# icyradio-upconverter.net
KiCad netlist of a schematic drawn in EAGLE
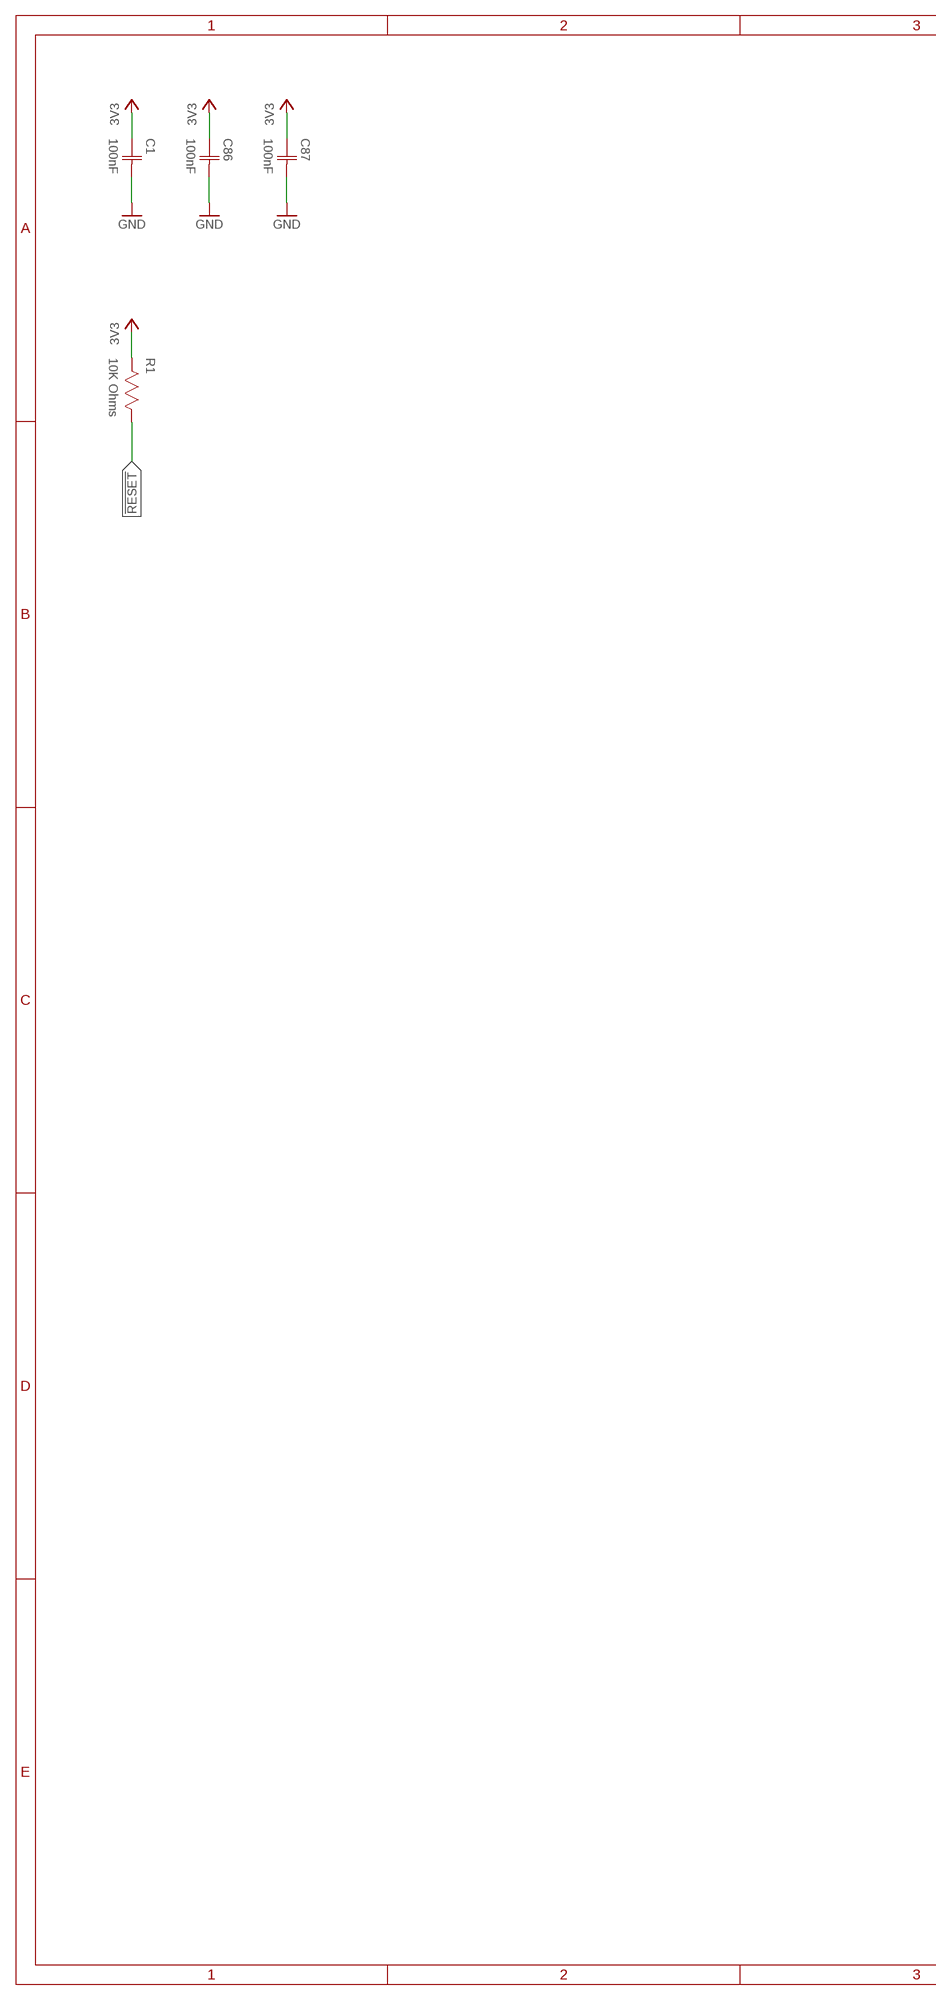
[diagram p0: schematic, sheet 1, part 1 of 2]
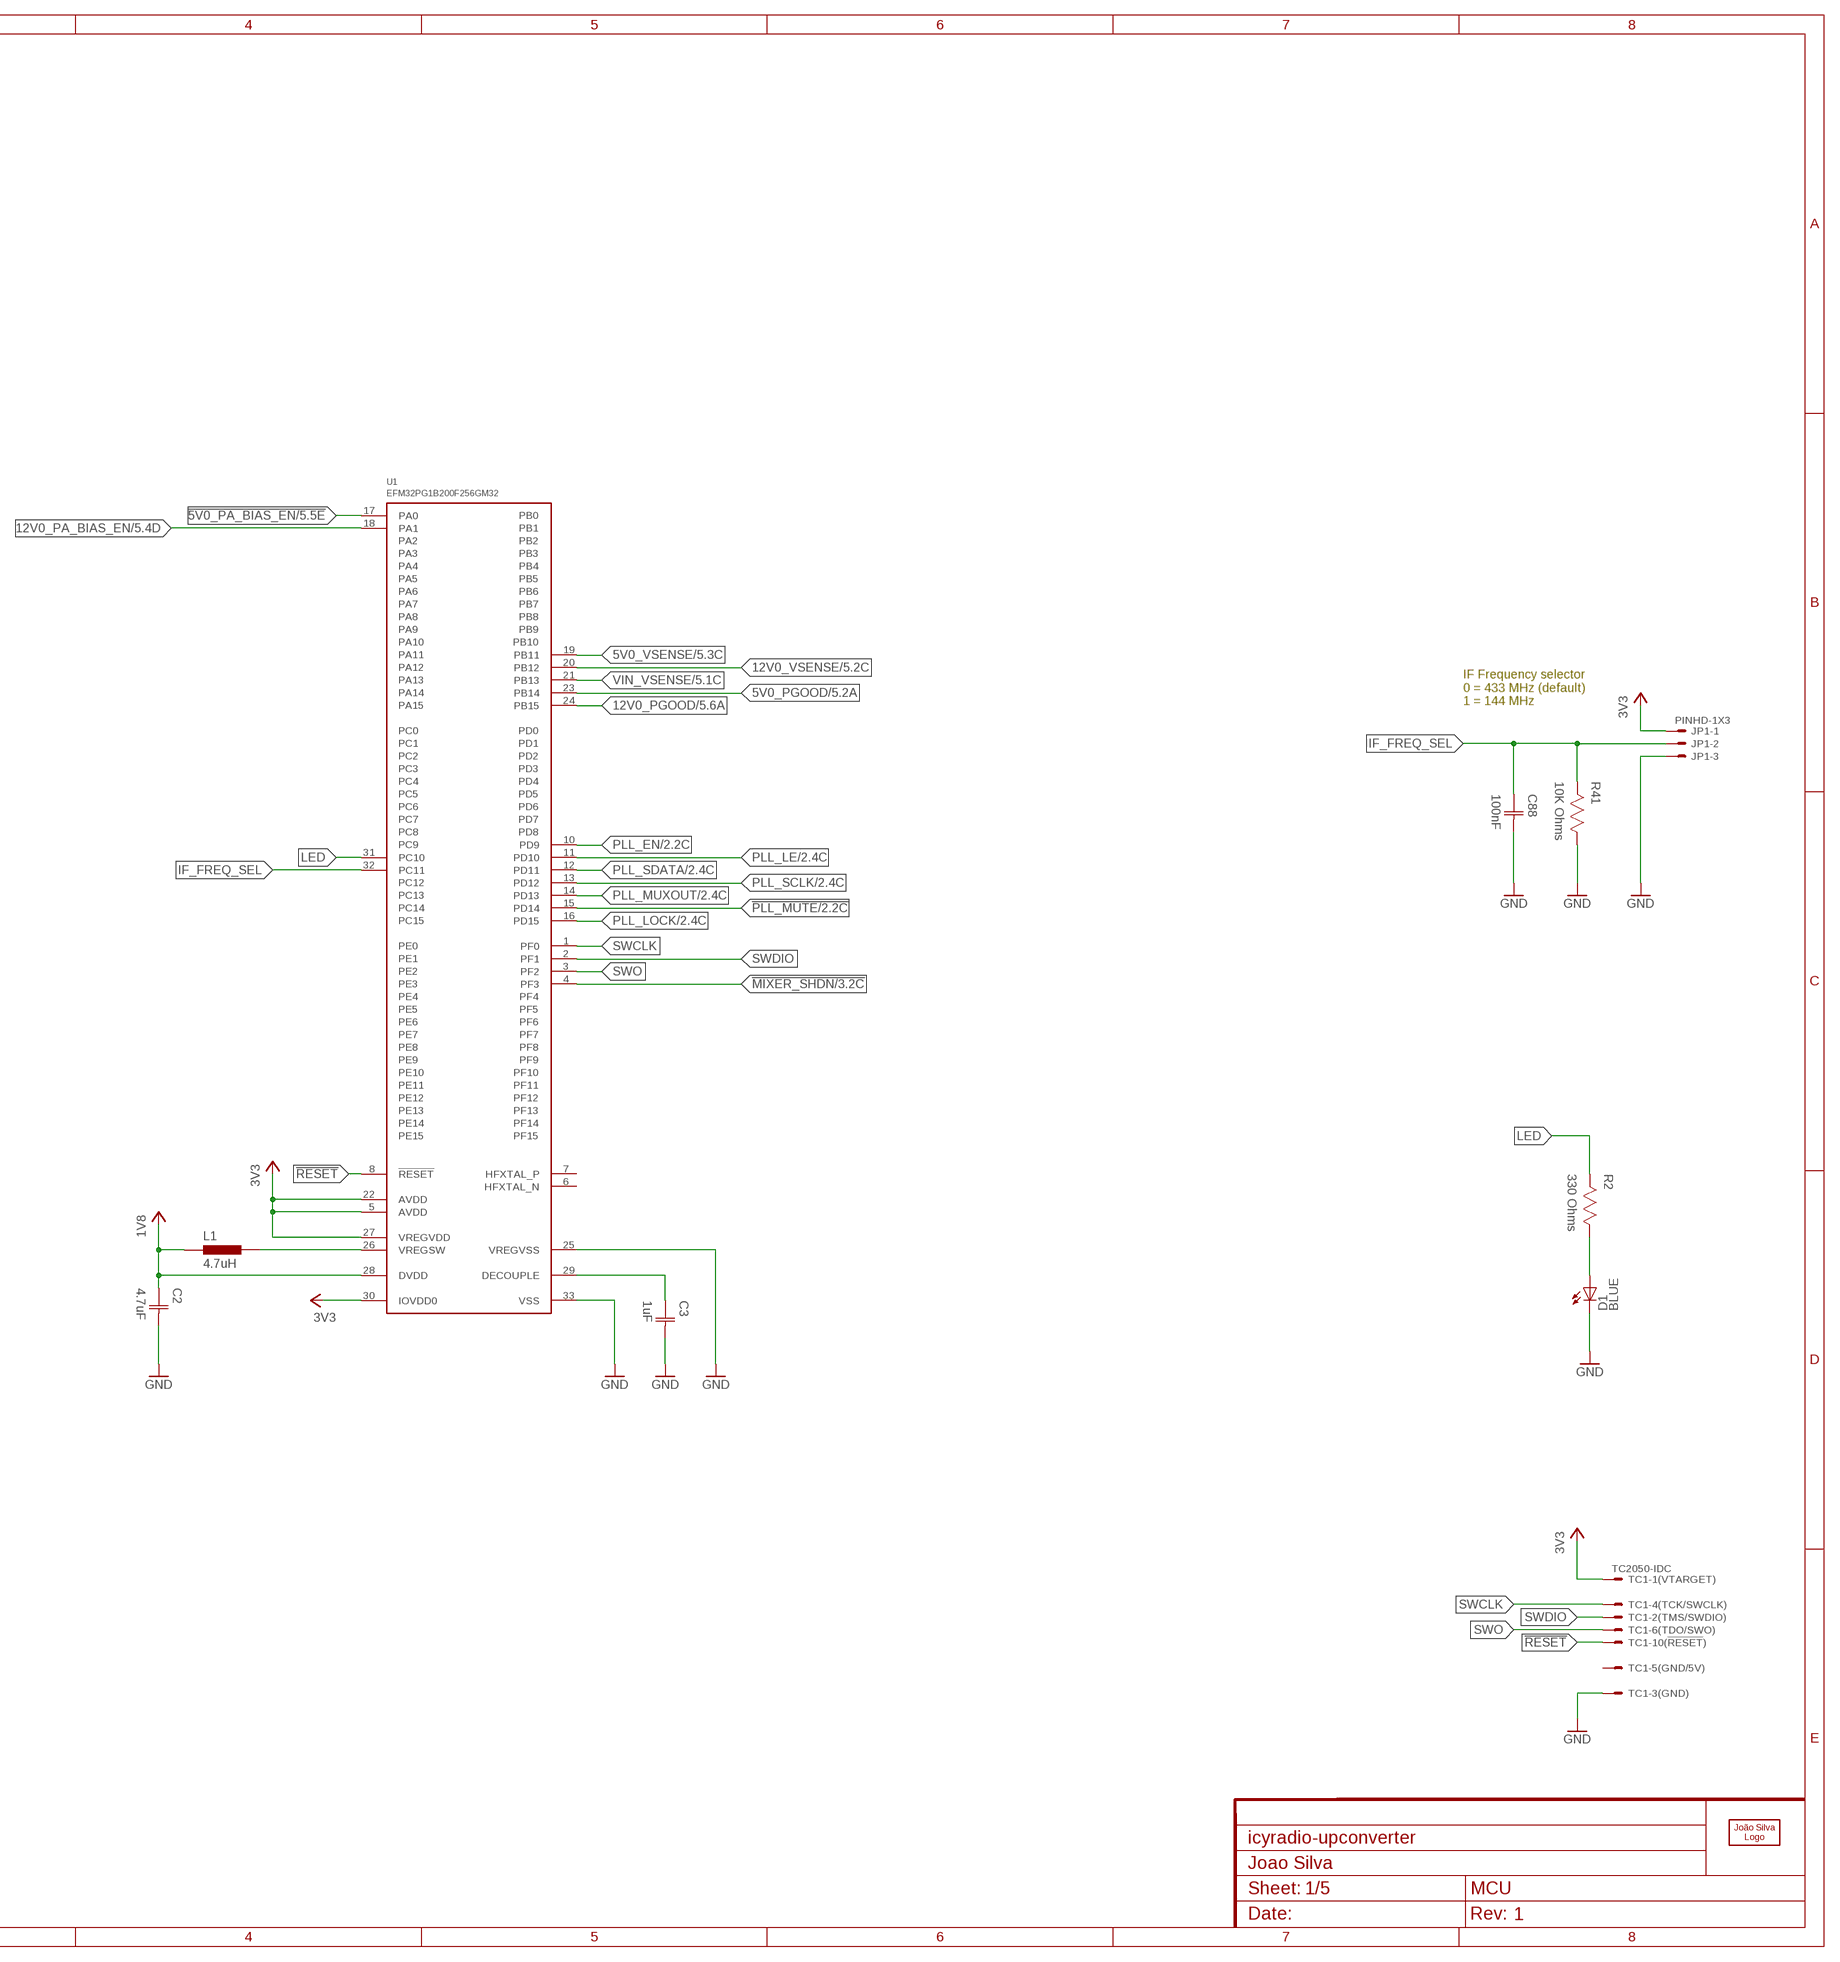
[diagram p1: schematic, sheet 1, part 2 of 2]
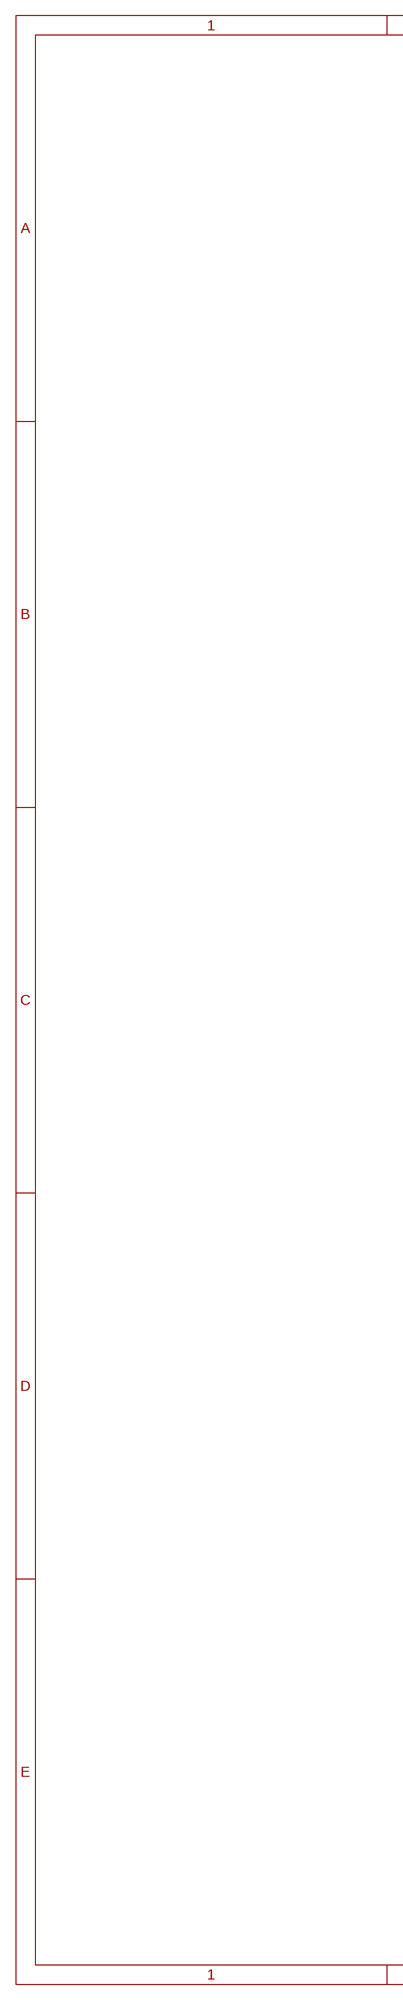
[diagram p2: schematic, sheet 2, part 1 of 2]
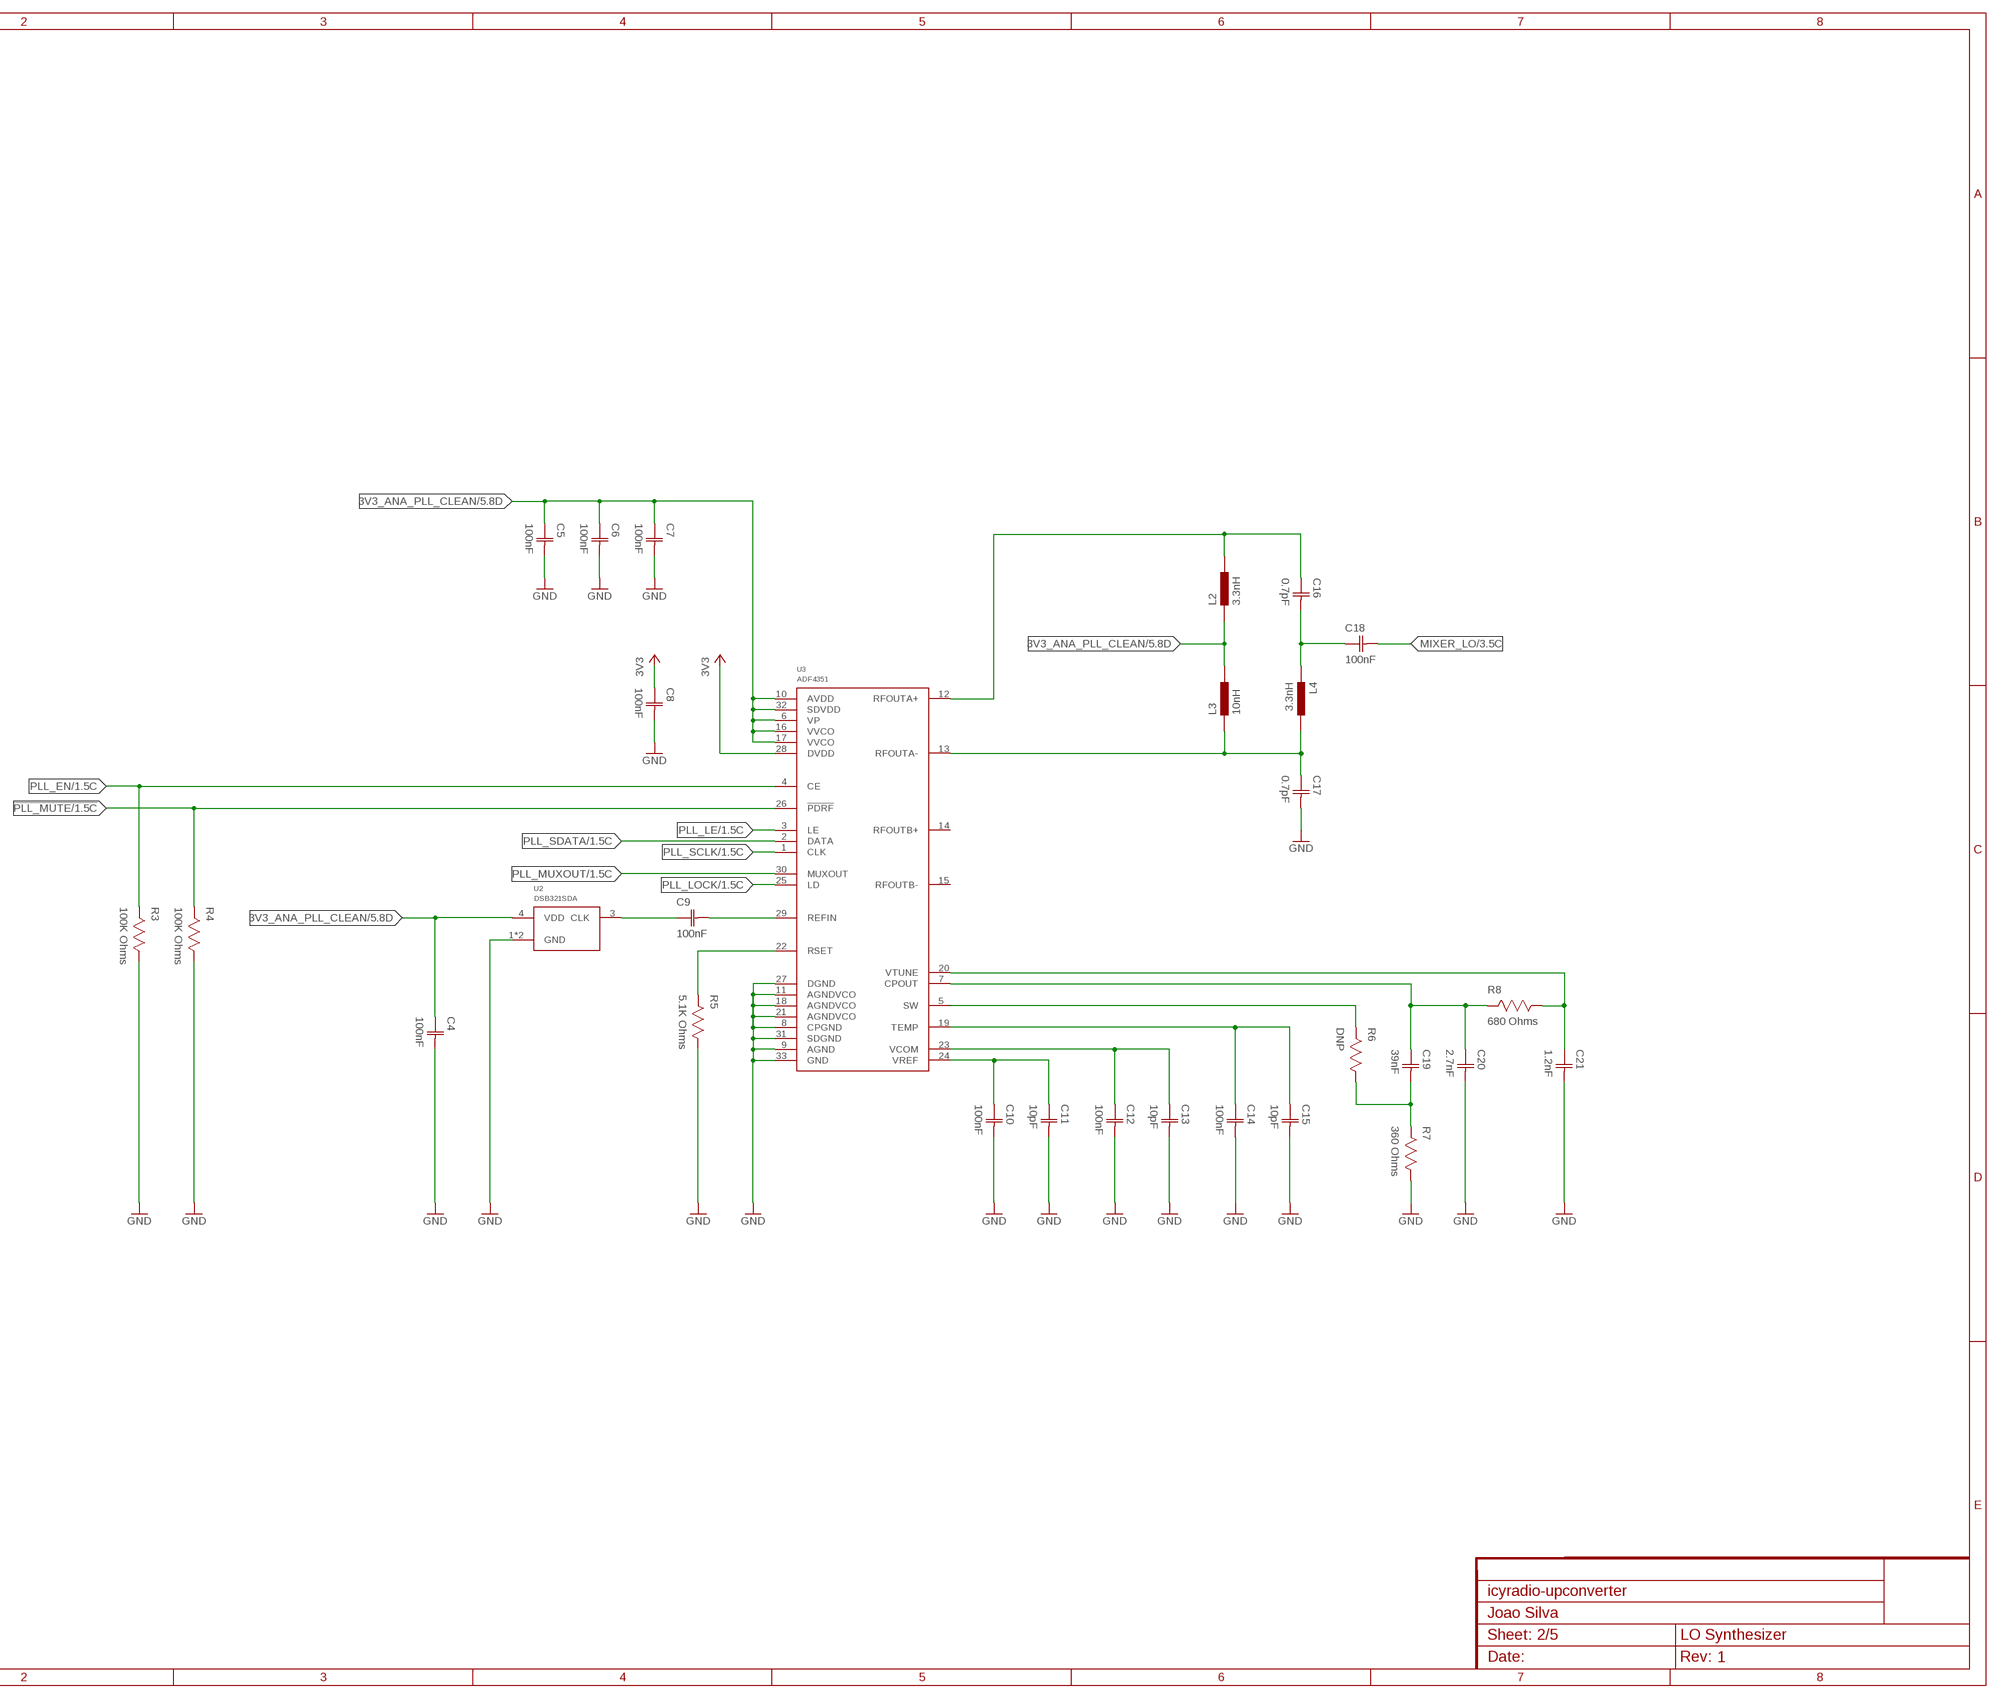
[diagram p3: schematic, sheet 2, part 2 of 2]
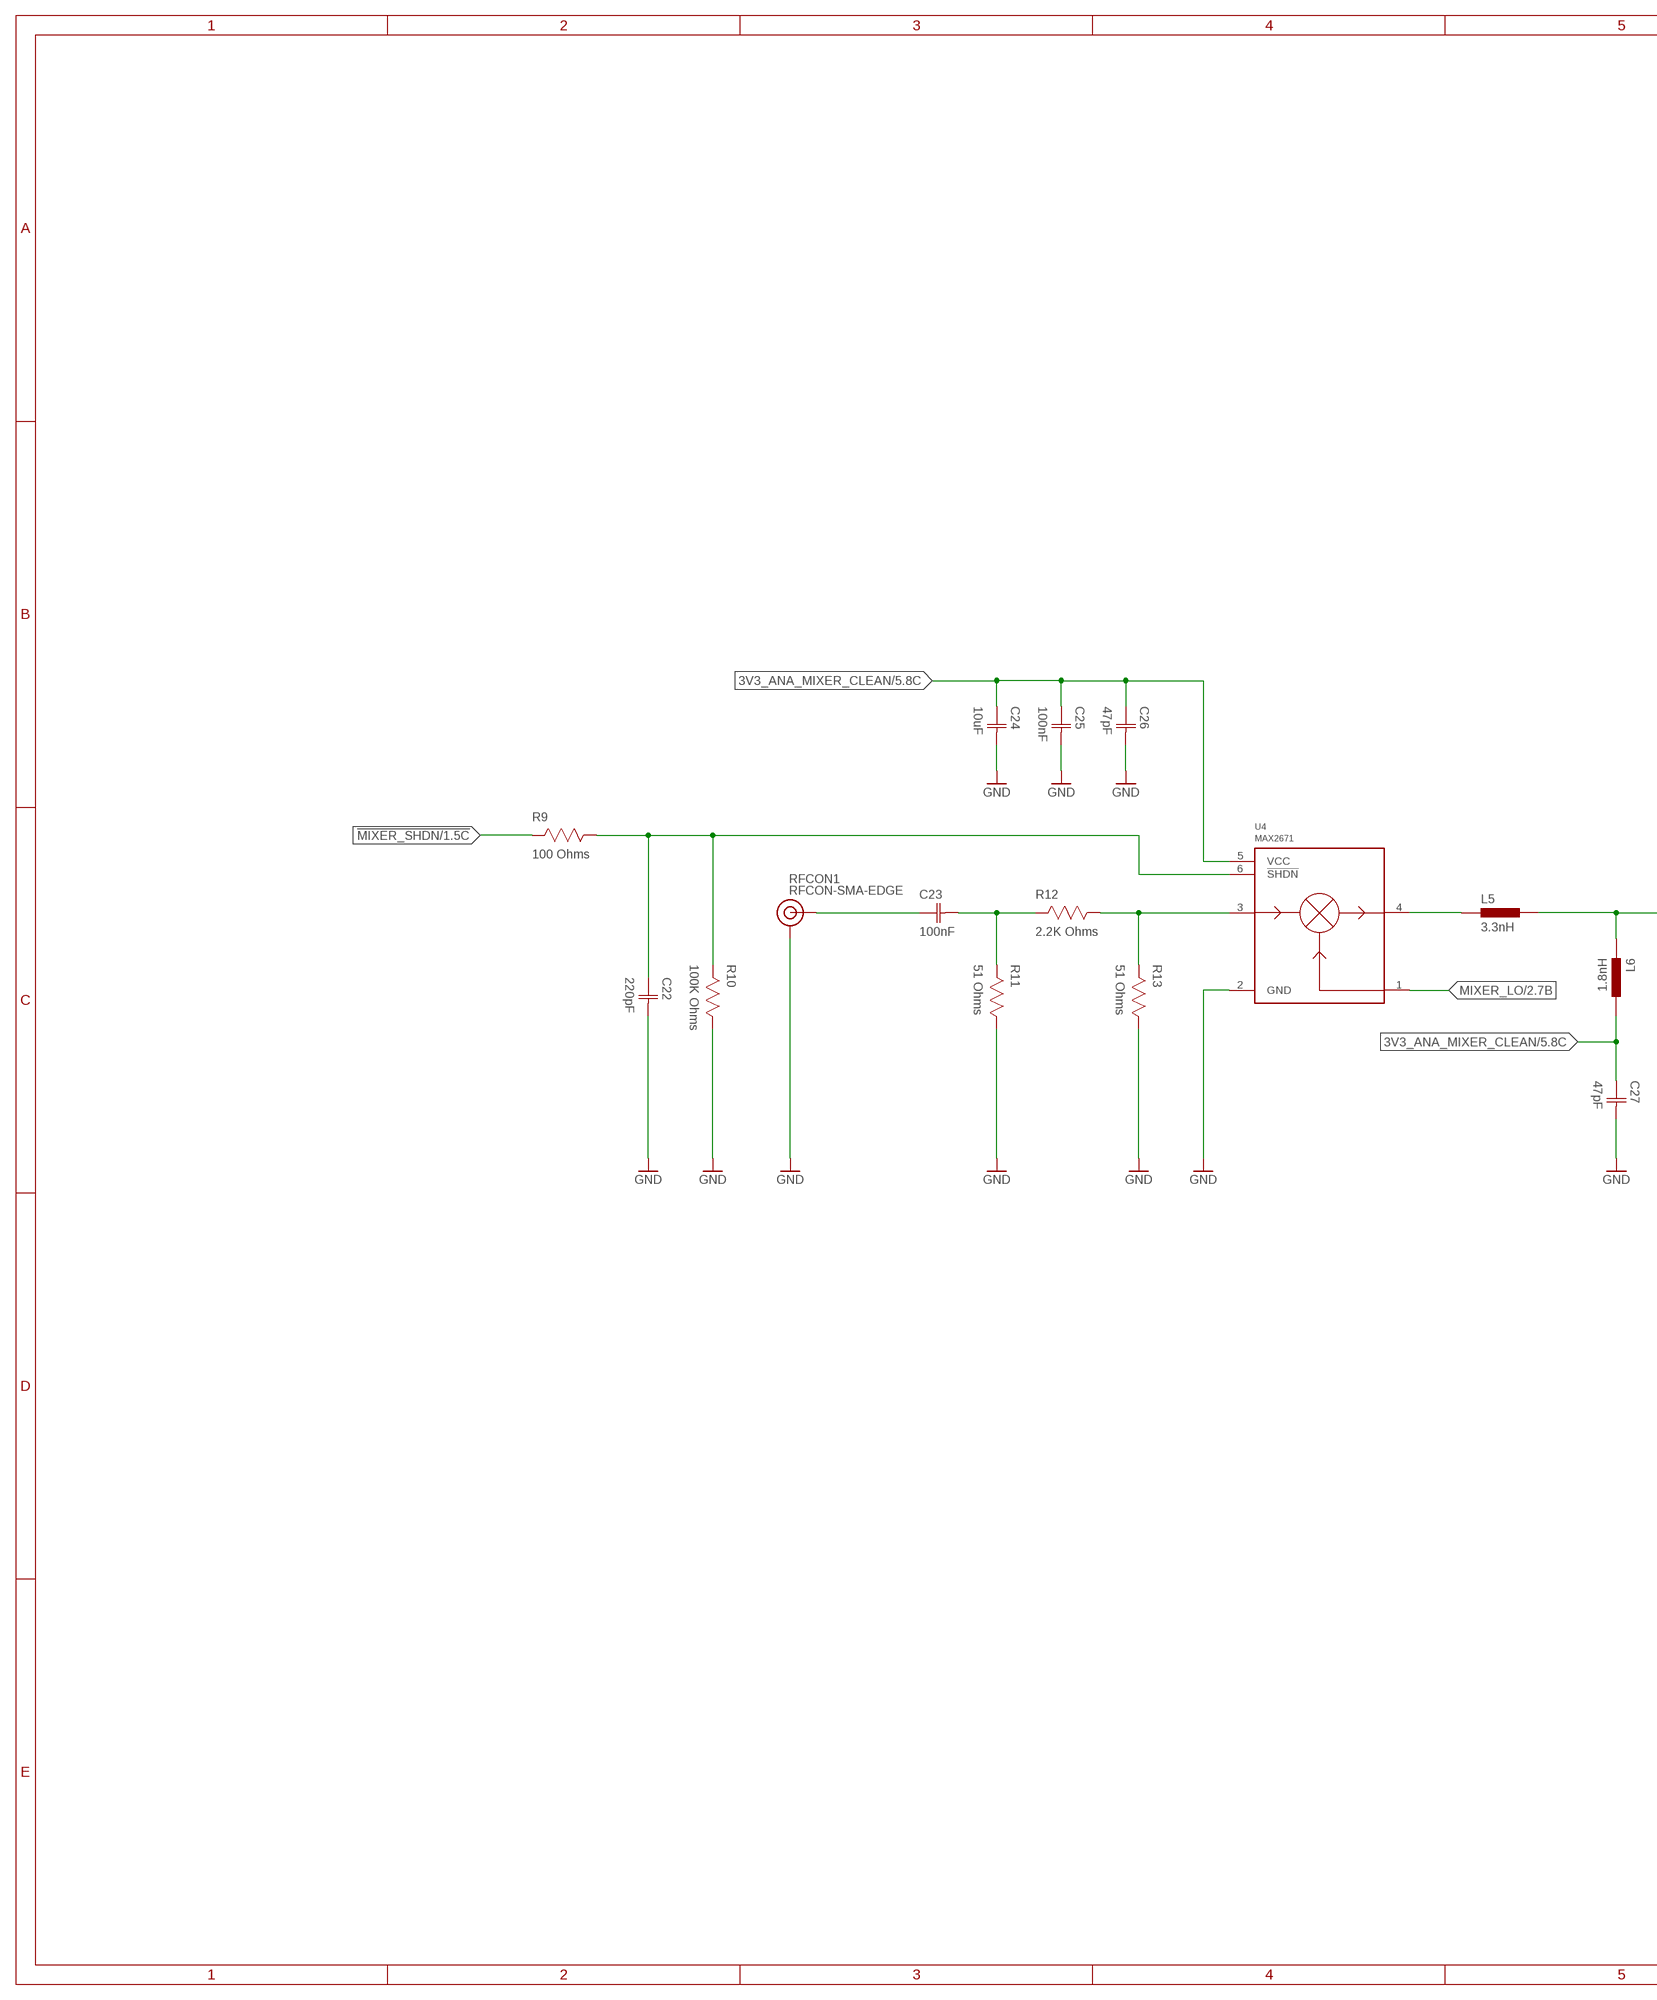
[diagram p4: schematic, sheet 3, part 1 of 2]
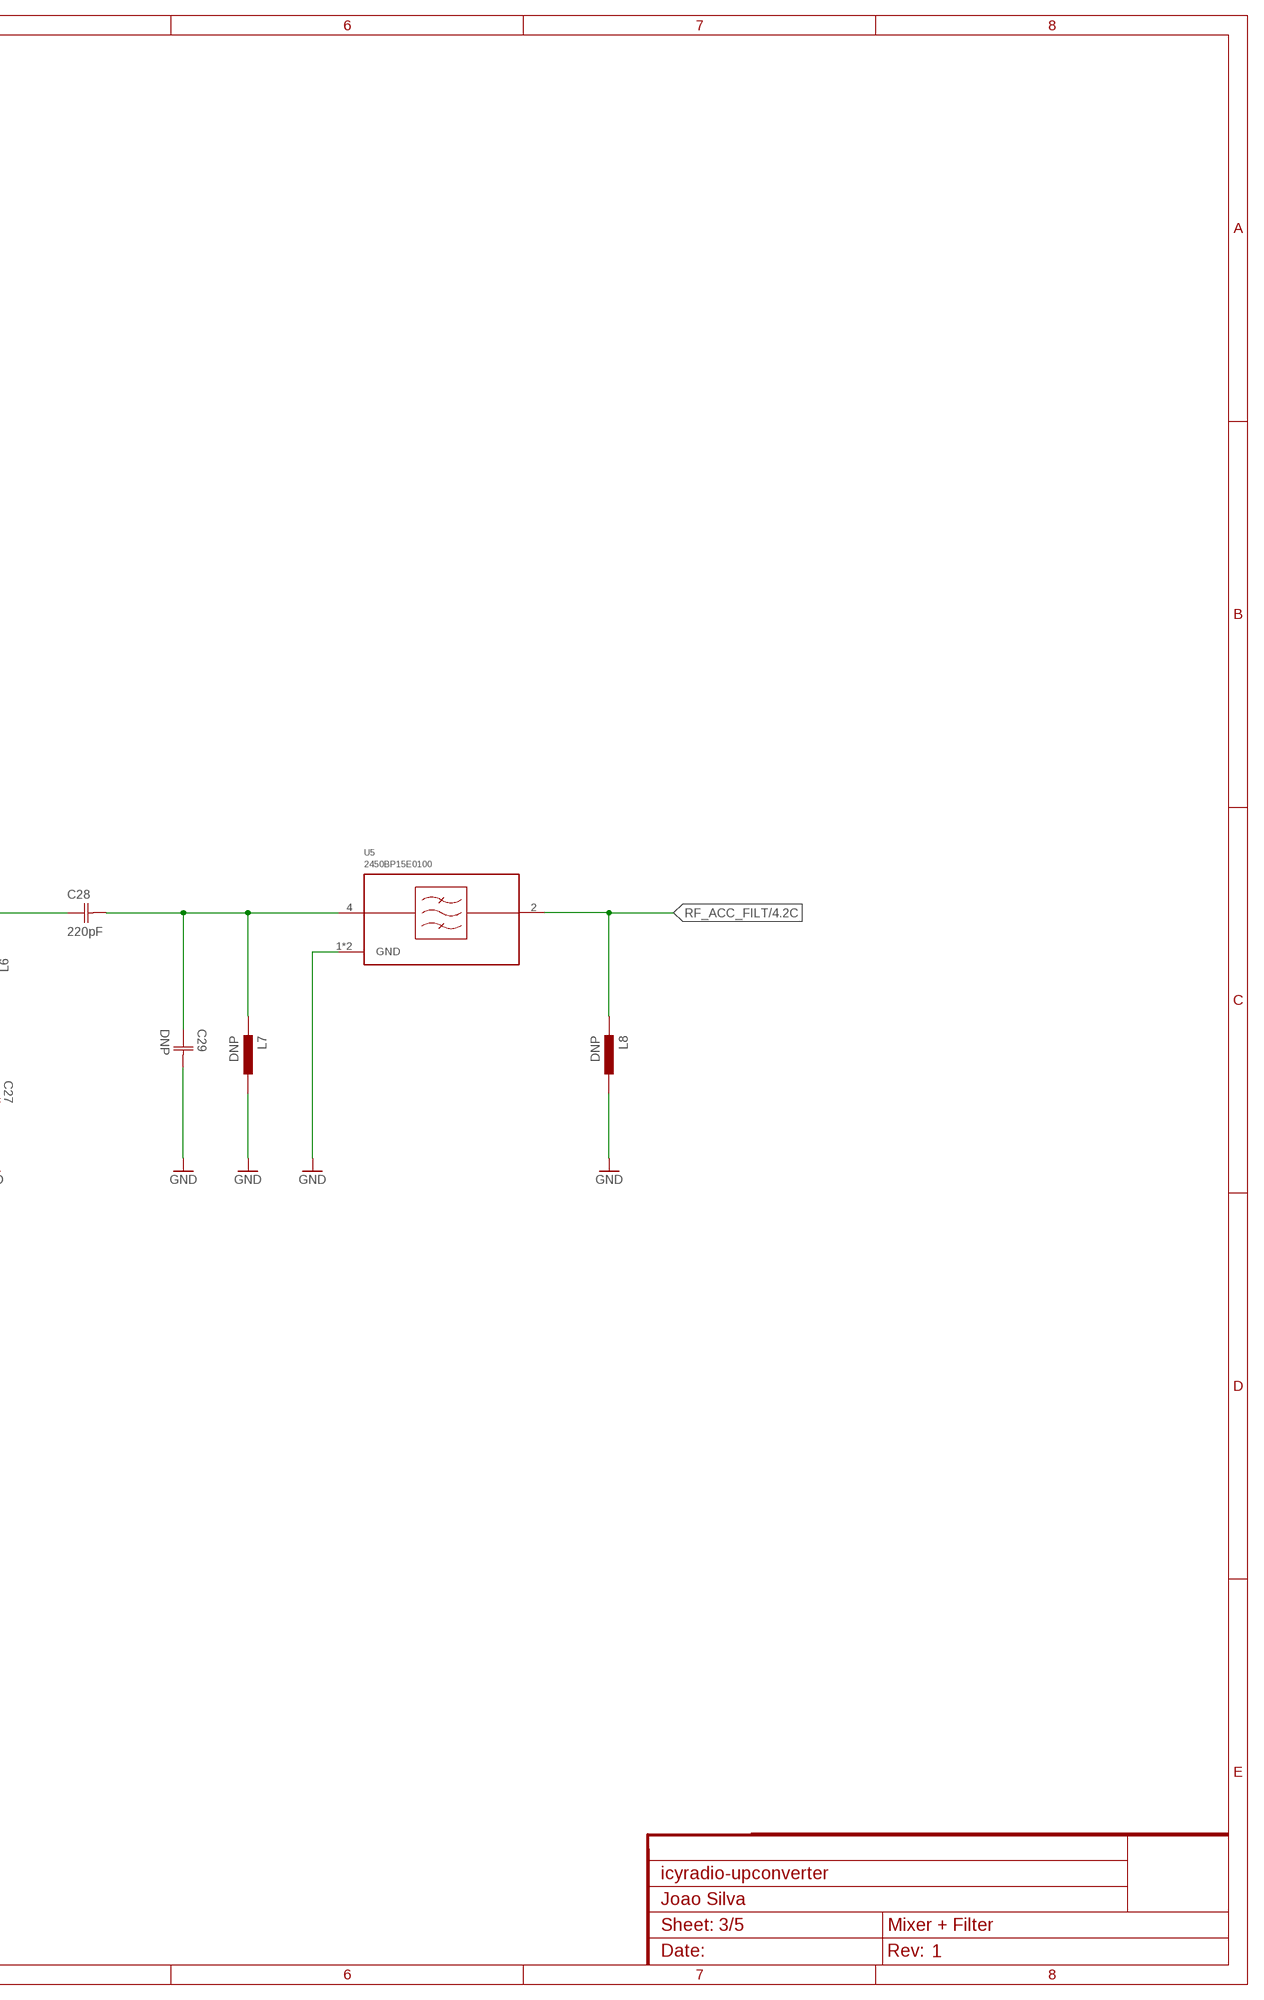
[diagram p5: schematic, sheet 3, part 2 of 2]
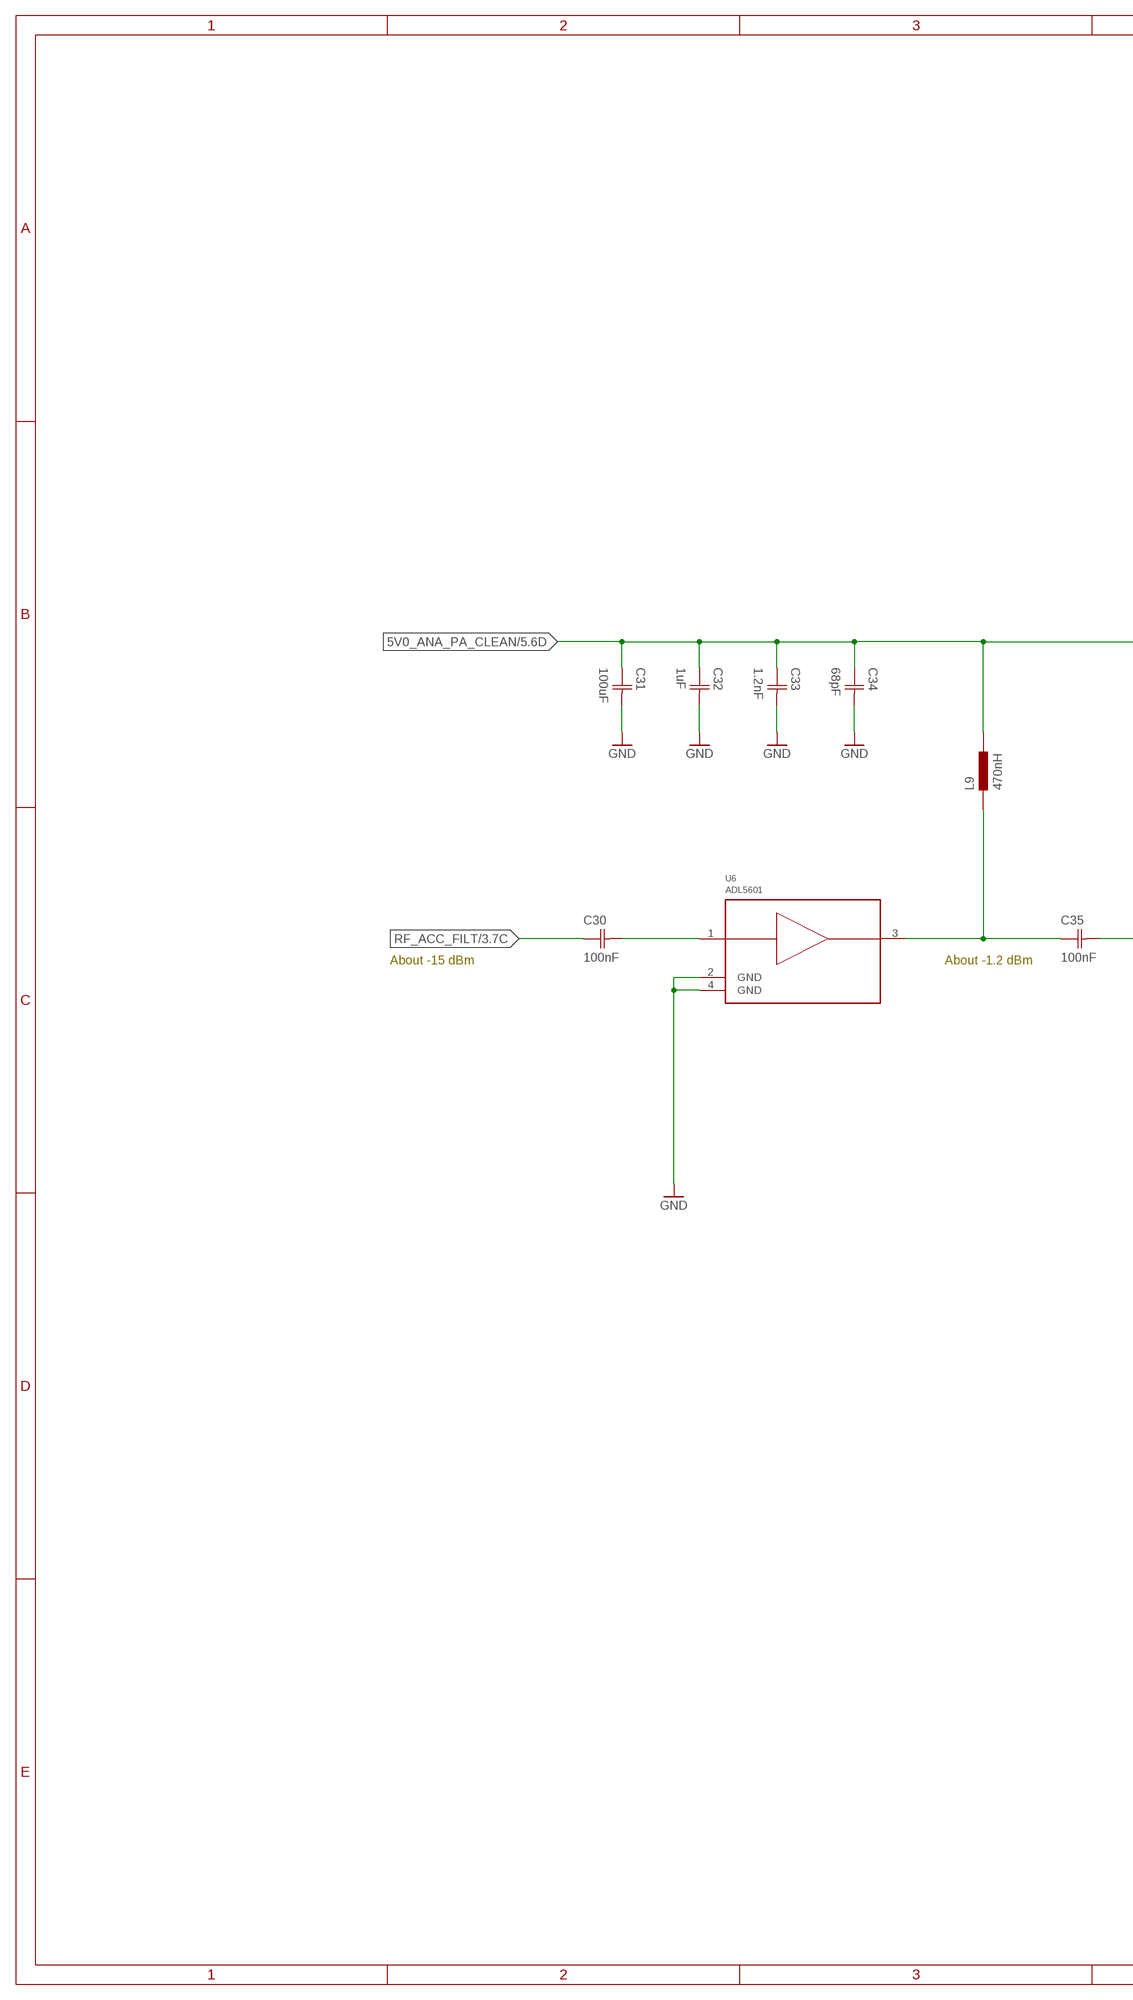
[diagram p6: schematic, sheet 4, part 1 of 2]
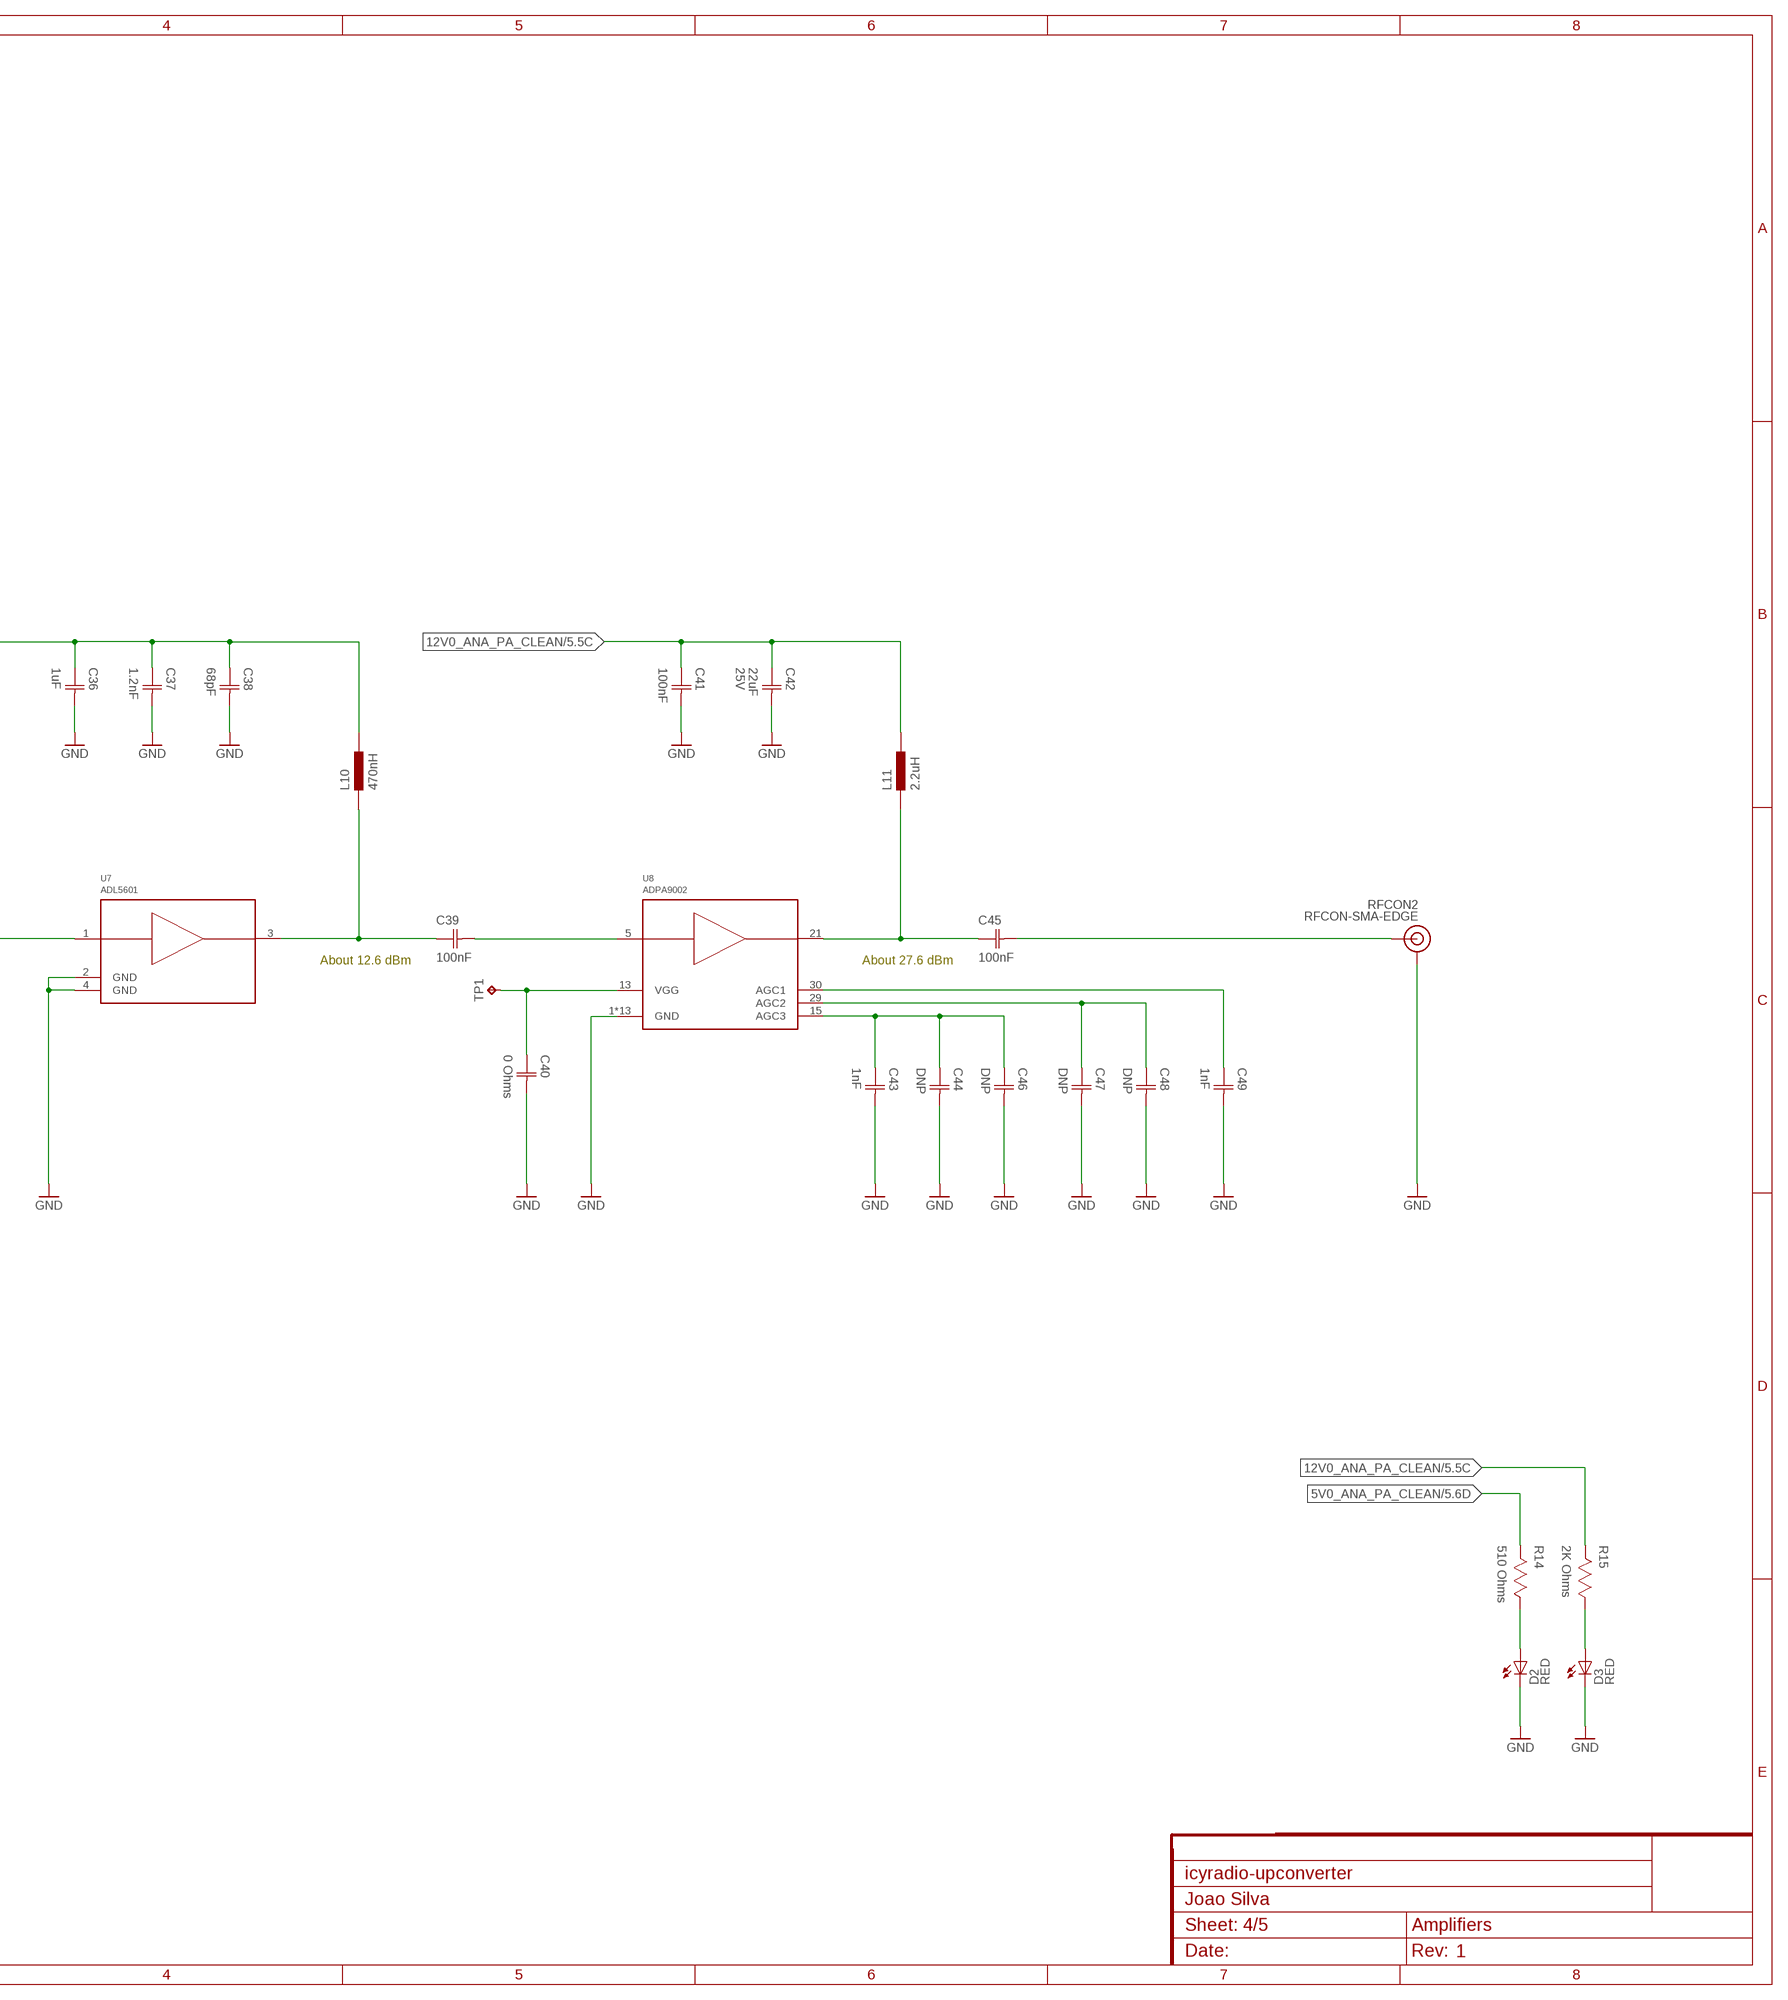
[diagram p7: schematic, sheet 4, part 2 of 2]
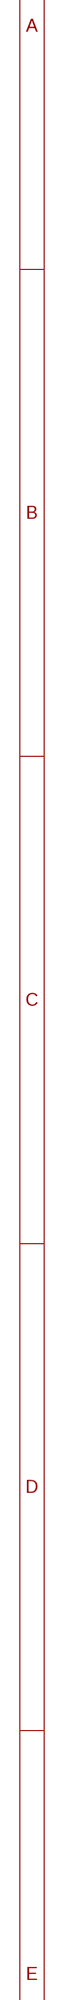
[diagram p8: schematic, sheet 5, part 1 of 2]
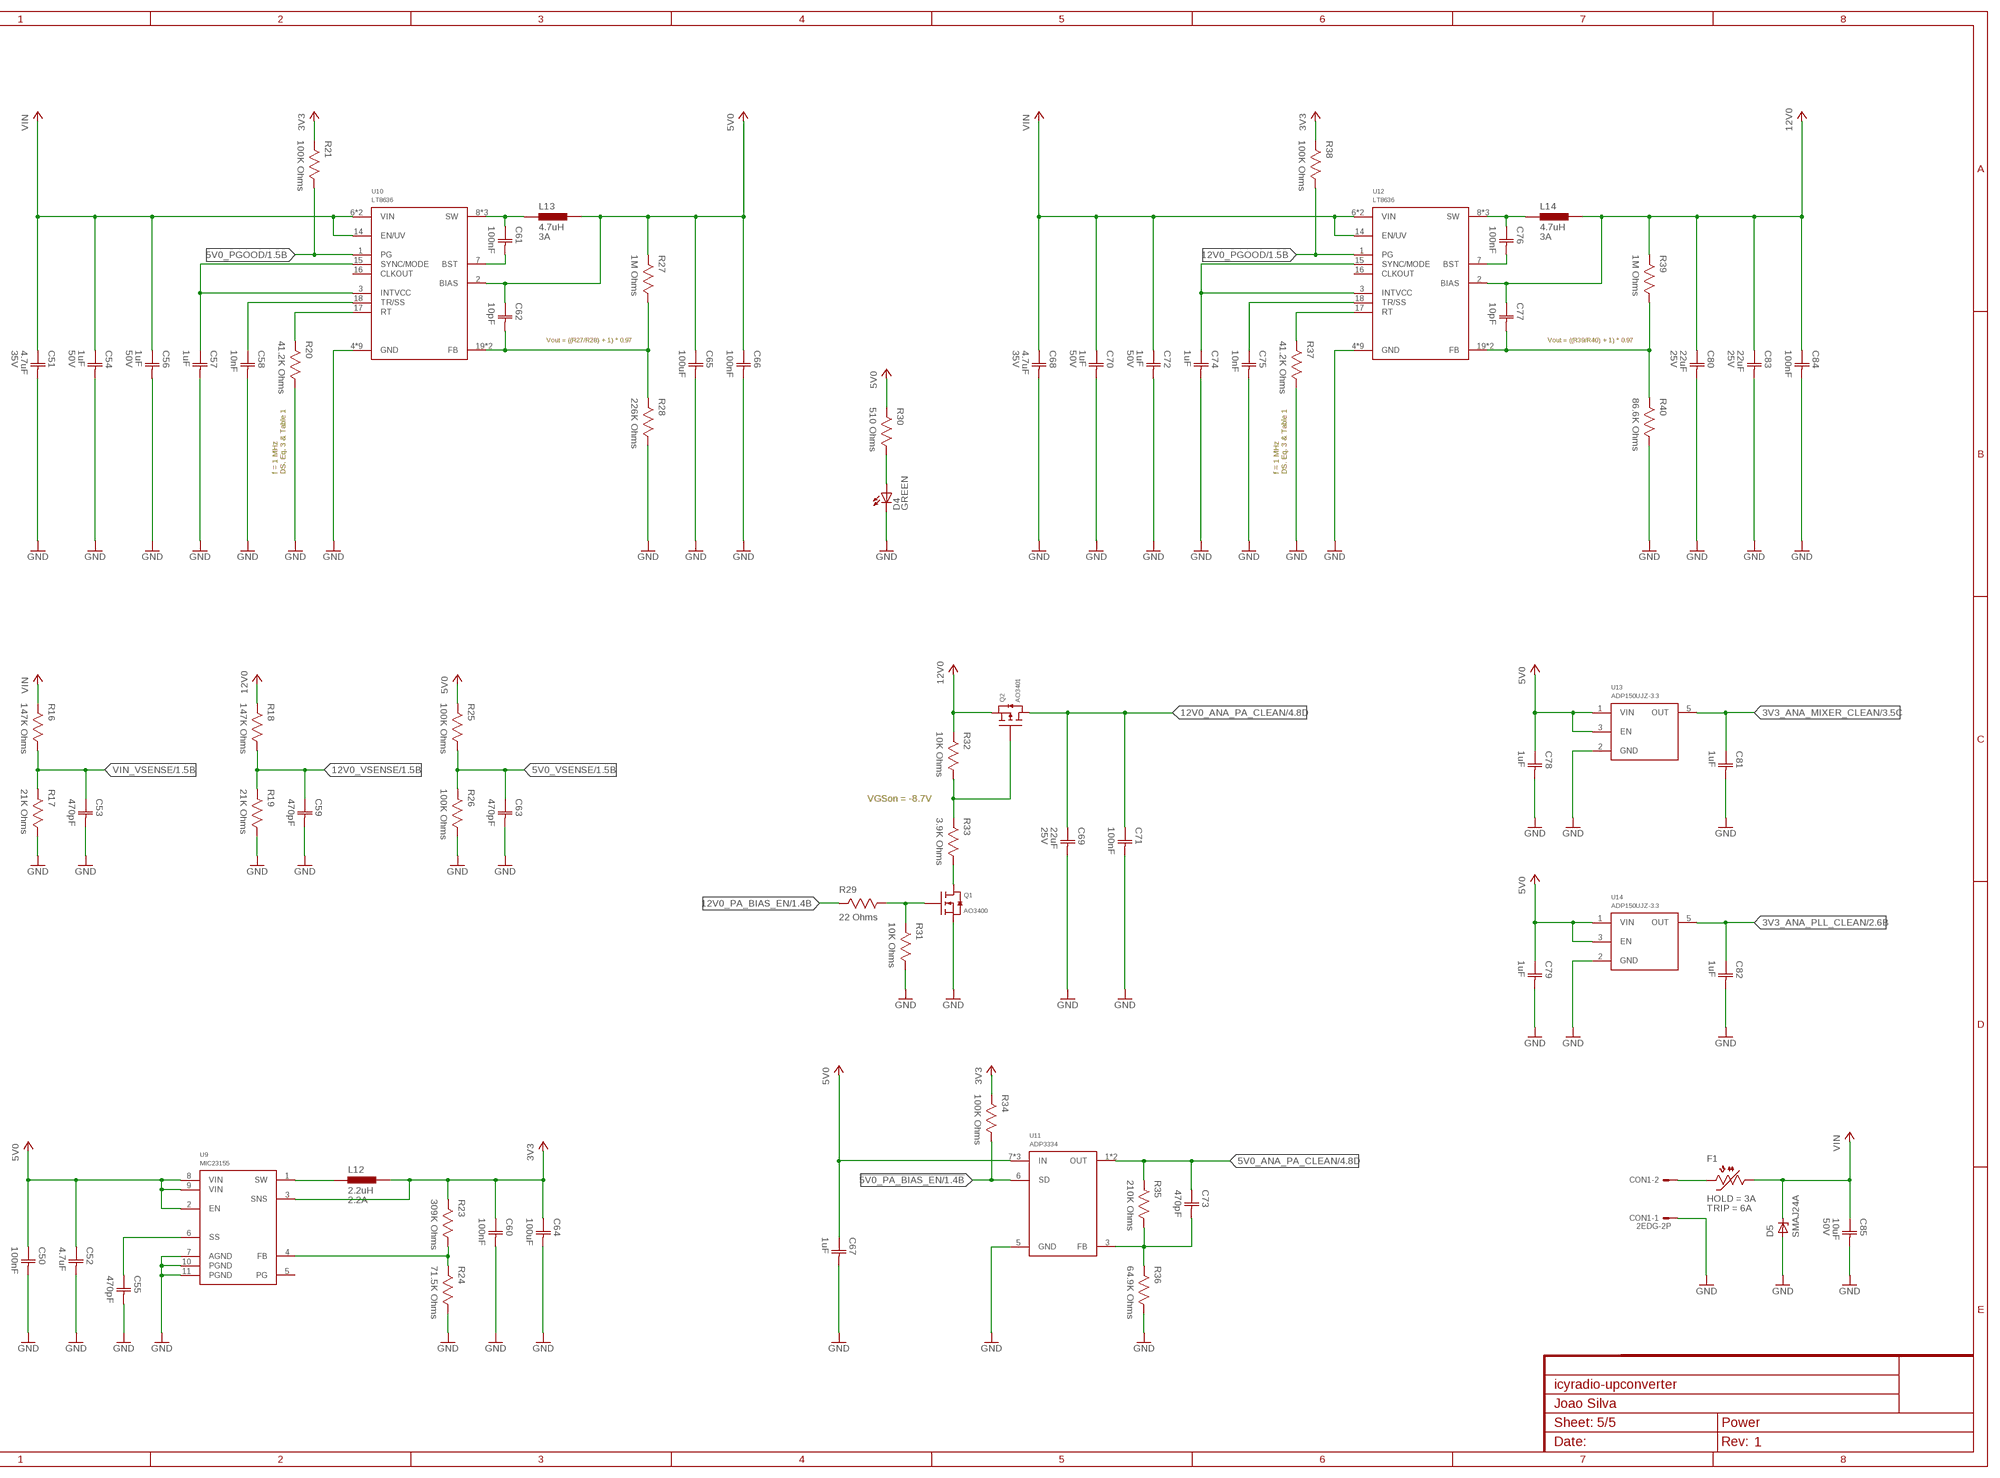
[diagram p9: schematic, sheet 5, part 2 of 2]

(export (version "E")
  (design (tool "Eeschema 10.0.6"))
  (components
    (comp (ref "C1")
      (value "100nF")
      (footprint "eagle-import:CAP0603")
      (libsource (lib "eagle-import") (part "CAPACITOR-0603"))
    )
    (comp (ref "C2")
      (value "4.7uF")
      (footprint "eagle-import:CAP0603")
      (libsource (lib "eagle-import") (part "CAPACITOR-0603"))
    )
    (comp (ref "C3")
      (value "1uF")
      (footprint "eagle-import:CAP0603")
      (libsource (lib "eagle-import") (part "CAPACITOR-0603"))
    )
    (comp (ref "C86")
      (value "100nF")
      (footprint "eagle-import:CAP0603")
      (libsource (lib "eagle-import") (part "CAPACITOR-0603"))
    )
    (comp (ref "C87")
      (value "100nF")
      (footprint "eagle-import:CAP0603")
      (libsource (lib "eagle-import") (part "CAPACITOR-0603"))
    )
    (comp (ref "C88")
      (value "100nF")
      (footprint "eagle-import:CAP0603")
      (libsource (lib "eagle-import") (part "CAPACITOR-0603"))
    )
    (comp (ref "D1")
      (value "LED0603")
      (footprint "eagle-import:0603")
      (fields (field (name "COLOR") "BLUE"))
      (libsource (lib "eagle-import") (part "LED0603"))
    )
    (comp (ref "JP1")
      (value "PINHD-1X3")
      (footprint "eagle-import:1X03")
      (libsource (lib "eagle-import") (part "PINHD-1X3"))
    )
    (comp (ref "L1")
      (value "4.7uH")
      (footprint "eagle-import:IND0603")
      (libsource (lib "eagle-import") (part "INDUCTOR-0603"))
    )
    (comp (ref "LOGO1")
      (value "JS-5MM")
      (footprint "eagle-import:JS_5MM")
      (libsource (lib "eagle-import") (part "JS-5MM"))
    )
    (comp (ref "R1")
      (value "10K Ohms")
      (footprint "eagle-import:RES0603")
      (libsource (lib "eagle-import") (part "RESISTOR-0603"))
    )
    (comp (ref "R2")
      (value "330 Ohms")
      (footprint "eagle-import:RES0603")
      (libsource (lib "eagle-import") (part "RESISTOR-0603"))
    )
    (comp (ref "R41")
      (value "10K Ohms")
      (footprint "eagle-import:RES0603")
      (libsource (lib "eagle-import") (part "RESISTOR-0603"))
    )
    (comp (ref "TC1")
      (value "TC2050-IDC")
      (footprint "eagle-import:TC2050-IDC")
      (libsource (lib "eagle-import") (part "TC2050-IDC"))
    )
    (comp (ref "U1")
      (value "EFM32PG1B200F256GM32")
      (footprint "eagle-import:QFN32_0.5P_JPG")
      (libsource (lib "eagle-import") (part "EFM32PG1B200FM32256G"))
    )
    (comp (ref "C30")
      (value "100nF")
      (footprint "eagle-import:CAP0603")
      (libsource (lib "eagle-import") (part "CAPACITOR-0603"))
    )
    (comp (ref "C31")
      (value "100uF")
      (footprint "eagle-import:CAP1206")
      (libsource (lib "eagle-import") (part "CAPACITOR-1206"))
    )
    (comp (ref "C32")
      (value "1uF")
      (footprint "eagle-import:CAP0603")
      (libsource (lib "eagle-import") (part "CAPACITOR-0603"))
    )
    (comp (ref "C33")
      (value "1.2nF")
      (footprint "eagle-import:CAP0603")
      (libsource (lib "eagle-import") (part "CAPACITOR-0603"))
    )
    (comp (ref "C34")
      (value "68pF")
      (footprint "eagle-import:CAP0603")
      (libsource (lib "eagle-import") (part "CAPACITOR-0603"))
    )
    (comp (ref "C35")
      (value "100nF")
      (footprint "eagle-import:CAP0603")
      (libsource (lib "eagle-import") (part "CAPACITOR-0603"))
    )
    (comp (ref "C36")
      (value "1uF")
      (footprint "eagle-import:CAP0603")
      (libsource (lib "eagle-import") (part "CAPACITOR-0603"))
    )
    (comp (ref "C37")
      (value "1.2nF")
      (footprint "eagle-import:CAP0603")
      (libsource (lib "eagle-import") (part "CAPACITOR-0603"))
    )
    (comp (ref "C38")
      (value "68pF")
      (footprint "eagle-import:CAP0603")
      (libsource (lib "eagle-import") (part "CAPACITOR-0603"))
    )
    (comp (ref "C39")
      (value "100nF")
      (footprint "eagle-import:CAP0603")
      (libsource (lib "eagle-import") (part "CAPACITOR-0603"))
    )
    (comp (ref "C40")
      (value "0 Ohms")
      (footprint "eagle-import:CAP0603")
      (libsource (lib "eagle-import") (part "CAPACITOR-0603"))
    )
    (comp (ref "C41")
      (value "100nF")
      (footprint "eagle-import:CAP0603")
      (libsource (lib "eagle-import") (part "CAPACITOR-0603"))
    )
    (comp (ref "C42")
      (value "22uF")
      (footprint "eagle-import:CAP1206")
      (fields (field (name "VOLTAGE") "25V"))
      (libsource (lib "eagle-import") (part "CAPACITOR-1206"))
    )
    (comp (ref "C43")
      (value "1nF")
      (footprint "eagle-import:CAP0603")
      (libsource (lib "eagle-import") (part "CAPACITOR-0603"))
    )
    (comp (ref "C44")
      (value "DNP")
      (footprint "eagle-import:CAP0603")
      (libsource (lib "eagle-import") (part "CAPACITOR-0603"))
    )
    (comp (ref "C45")
      (value "100nF")
      (footprint "eagle-import:CAP0603")
      (libsource (lib "eagle-import") (part "CAPACITOR-0603"))
    )
    (comp (ref "C46")
      (value "DNP")
      (footprint "eagle-import:CAP0603")
      (libsource (lib "eagle-import") (part "CAPACITOR-0603"))
    )
    (comp (ref "C47")
      (value "DNP")
      (footprint "eagle-import:CAP0603")
      (libsource (lib "eagle-import") (part "CAPACITOR-0603"))
    )
    (comp (ref "C48")
      (value "DNP")
      (footprint "eagle-import:CAP0603")
      (libsource (lib "eagle-import") (part "CAPACITOR-0603"))
    )
    (comp (ref "C49")
      (value "1nF")
      (footprint "eagle-import:CAP0603")
      (libsource (lib "eagle-import") (part "CAPACITOR-0603"))
    )
    (comp (ref "D2")
      (value "LED0603")
      (footprint "eagle-import:0603")
      (fields (field (name "COLOR") "RED"))
      (libsource (lib "eagle-import") (part "LED0603"))
    )
    (comp (ref "D3")
      (value "LED0603")
      (footprint "eagle-import:0603")
      (fields (field (name "COLOR") "RED"))
      (libsource (lib "eagle-import") (part "LED0603"))
    )
    (comp (ref "L9")
      (value "470nH")
      (footprint "eagle-import:IND0603")
      (libsource (lib "eagle-import") (part "INDUCTOR-0603"))
    )
    (comp (ref "L10")
      (value "470nH")
      (footprint "eagle-import:IND0603")
      (libsource (lib "eagle-import") (part "INDUCTOR-0603"))
    )
    (comp (ref "L11")
      (value "2.2uH")
      (footprint "eagle-import:IND0603")
      (libsource (lib "eagle-import") (part "INDUCTOR-0603"))
    )
    (comp (ref "R14")
      (value "510 Ohms")
      (footprint "eagle-import:RES0603")
      (libsource (lib "eagle-import") (part "RESISTOR-0603"))
    )
    (comp (ref "R15")
      (value "2K Ohms")
      (footprint "eagle-import:RES0603")
      (libsource (lib "eagle-import") (part "RESISTOR-0603"))
    )
    (comp (ref "RFCON2")
      (value "RFCON-SMA-EDGE")
      (footprint "eagle-import:SMA-EDGE")
      (libsource (lib "eagle-import") (part "RFCON-SMA-EDGE"))
    )
    (comp (ref "TP1")
      (value "TESTPOINT-1.27MM")
      (footprint "eagle-import:PAD1.27MM")
      (libsource (lib "eagle-import") (part "TESTPOINT-1.27MM"))
    )
    (comp (ref "U6")
      (value "ADL5601")
      (footprint "eagle-import:SOT89")
      (libsource (lib "eagle-import") (part "ADL5?601"))
    )
    (comp (ref "U7")
      (value "ADL5601")
      (footprint "eagle-import:SOT89")
      (libsource (lib "eagle-import") (part "ADL5?601"))
    )
    (comp (ref "U8")
      (value "ADPA9002")
      (footprint "eagle-import:QFN32")
      (libsource (lib "eagle-import") (part "ADPA9002"))
    )
    (comp (ref "C4")
      (value "100nF")
      (footprint "eagle-import:CAP0603")
      (libsource (lib "eagle-import") (part "CAPACITOR-0603"))
    )
    (comp (ref "C5")
      (value "100nF")
      (footprint "eagle-import:CAP0603")
      (libsource (lib "eagle-import") (part "CAPACITOR-0603"))
    )
    (comp (ref "C6")
      (value "100nF")
      (footprint "eagle-import:CAP0603")
      (libsource (lib "eagle-import") (part "CAPACITOR-0603"))
    )
    (comp (ref "C7")
      (value "100nF")
      (footprint "eagle-import:CAP0603")
      (libsource (lib "eagle-import") (part "CAPACITOR-0603"))
    )
    (comp (ref "C8")
      (value "100nF")
      (footprint "eagle-import:CAP0603")
      (libsource (lib "eagle-import") (part "CAPACITOR-0603"))
    )
    (comp (ref "C9")
      (value "100nF")
      (footprint "eagle-import:CAP0603")
      (libsource (lib "eagle-import") (part "CAPACITOR-0603"))
    )
    (comp (ref "C10")
      (value "100nF")
      (footprint "eagle-import:CAP0603")
      (libsource (lib "eagle-import") (part "CAPACITOR-0603"))
    )
    (comp (ref "C11")
      (value "10pF")
      (footprint "eagle-import:CAP0603")
      (libsource (lib "eagle-import") (part "CAPACITOR-0603"))
    )
    (comp (ref "C12")
      (value "100nF")
      (footprint "eagle-import:CAP0603")
      (libsource (lib "eagle-import") (part "CAPACITOR-0603"))
    )
    (comp (ref "C13")
      (value "10pF")
      (footprint "eagle-import:CAP0603")
      (libsource (lib "eagle-import") (part "CAPACITOR-0603"))
    )
    (comp (ref "C14")
      (value "100nF")
      (footprint "eagle-import:CAP0603")
      (libsource (lib "eagle-import") (part "CAPACITOR-0603"))
    )
    (comp (ref "C15")
      (value "10pF")
      (footprint "eagle-import:CAP0603")
      (libsource (lib "eagle-import") (part "CAPACITOR-0603"))
    )
    (comp (ref "C16")
      (value "0.7pF")
      (footprint "eagle-import:CAP0603")
      (libsource (lib "eagle-import") (part "CAPACITOR-0603"))
    )
    (comp (ref "C17")
      (value "0.7pF")
      (footprint "eagle-import:CAP0603")
      (libsource (lib "eagle-import") (part "CAPACITOR-0603"))
    )
    (comp (ref "C18")
      (value "100nF")
      (footprint "eagle-import:CAP0603")
      (libsource (lib "eagle-import") (part "CAPACITOR-0603"))
    )
    (comp (ref "C19")
      (value "39nF")
      (footprint "eagle-import:CAP0603")
      (libsource (lib "eagle-import") (part "CAPACITOR-0603"))
    )
    (comp (ref "C20")
      (value "2.7nF")
      (footprint "eagle-import:CAP0603")
      (libsource (lib "eagle-import") (part "CAPACITOR-0603"))
    )
    (comp (ref "C21")
      (value "1.2nF")
      (footprint "eagle-import:CAP0603")
      (libsource (lib "eagle-import") (part "CAPACITOR-0603"))
    )
    (comp (ref "L2")
      (value "3.3nH")
      (footprint "eagle-import:IND0603")
      (libsource (lib "eagle-import") (part "INDUCTOR-0603"))
    )
    (comp (ref "L3")
      (value "10nH")
      (footprint "eagle-import:IND0603")
      (libsource (lib "eagle-import") (part "INDUCTOR-0603"))
    )
    (comp (ref "L4")
      (value "3.3nH")
      (footprint "eagle-import:IND0603")
      (libsource (lib "eagle-import") (part "INDUCTOR-0603"))
    )
    (comp (ref "R3")
      (value "100K Ohms")
      (footprint "eagle-import:RES0603")
      (libsource (lib "eagle-import") (part "RESISTOR-0603"))
    )
    (comp (ref "R4")
      (value "100K Ohms")
      (footprint "eagle-import:RES0603")
      (libsource (lib "eagle-import") (part "RESISTOR-0603"))
    )
    (comp (ref "R5")
      (value "5.1K Ohms")
      (footprint "eagle-import:RES0603")
      (libsource (lib "eagle-import") (part "RESISTOR-0603"))
    )
    (comp (ref "R6")
      (value "DNP")
      (footprint "eagle-import:RES0603")
      (libsource (lib "eagle-import") (part "RESISTOR-0603"))
    )
    (comp (ref "R7")
      (value "360 Ohms")
      (footprint "eagle-import:RES0603")
      (libsource (lib "eagle-import") (part "RESISTOR-0603"))
    )
    (comp (ref "R8")
      (value "680 Ohms")
      (footprint "eagle-import:RES0603")
      (libsource (lib "eagle-import") (part "RESISTOR-0603"))
    )
    (comp (ref "U2")
      (value "DSB321SDA")
      (footprint "eagle-import:TCXO-3225")
      (libsource (lib "eagle-import") (part "DSB321SDA"))
    )
    (comp (ref "U3")
      (value "ADF4351")
      (footprint "eagle-import:QFN32")
      (libsource (lib "eagle-import") (part "ADF4351"))
    )
    (comp (ref "C22")
      (value "220pF")
      (footprint "eagle-import:CAP0603")
      (libsource (lib "eagle-import") (part "CAPACITOR-0603"))
    )
    (comp (ref "C23")
      (value "100nF")
      (footprint "eagle-import:CAP0603")
      (libsource (lib "eagle-import") (part "CAPACITOR-0603"))
    )
    (comp (ref "C24")
      (value "10uF")
      (footprint "eagle-import:CAP0603")
      (libsource (lib "eagle-import") (part "CAPACITOR-0603"))
    )
    (comp (ref "C25")
      (value "100nF")
      (footprint "eagle-import:CAP0603")
      (libsource (lib "eagle-import") (part "CAPACITOR-0603"))
    )
    (comp (ref "C26")
      (value "47pF")
      (footprint "eagle-import:CAP0603")
      (libsource (lib "eagle-import") (part "CAPACITOR-0603"))
    )
    (comp (ref "C27")
      (value "47pF")
      (footprint "eagle-import:CAP0603")
      (libsource (lib "eagle-import") (part "CAPACITOR-0603"))
    )
    (comp (ref "C28")
      (value "220pF")
      (footprint "eagle-import:CAP0603")
      (libsource (lib "eagle-import") (part "CAPACITOR-0603"))
    )
    (comp (ref "C29")
      (value "DNP")
      (footprint "eagle-import:CAP0603")
      (libsource (lib "eagle-import") (part "CAPACITOR-0603"))
    )
    (comp (ref "L5")
      (value "3.3nH")
      (footprint "eagle-import:IND0603")
      (libsource (lib "eagle-import") (part "INDUCTOR-0603"))
    )
    (comp (ref "L6")
      (value "1.8nH")
      (footprint "eagle-import:IND0603")
      (libsource (lib "eagle-import") (part "INDUCTOR-0603"))
    )
    (comp (ref "L7")
      (value "DNP")
      (footprint "eagle-import:IND0603")
      (libsource (lib "eagle-import") (part "INDUCTOR-0603"))
    )
    (comp (ref "L8")
      (value "DNP")
      (footprint "eagle-import:IND0603")
      (libsource (lib "eagle-import") (part "INDUCTOR-0603"))
    )
    (comp (ref "R9")
      (value "100 Ohms")
      (footprint "eagle-import:RES0603")
      (libsource (lib "eagle-import") (part "RESISTOR-0603"))
    )
    (comp (ref "R10")
      (value "100K Ohms")
      (footprint "eagle-import:RES0603")
      (libsource (lib "eagle-import") (part "RESISTOR-0603"))
    )
    (comp (ref "R11")
      (value "51 Ohms")
      (footprint "eagle-import:RES0603")
      (libsource (lib "eagle-import") (part "RESISTOR-0603"))
    )
    (comp (ref "R12")
      (value "2.2K Ohms")
      (footprint "eagle-import:RES0603")
      (libsource (lib "eagle-import") (part "RESISTOR-0603"))
    )
    (comp (ref "R13")
      (value "51 Ohms")
      (footprint "eagle-import:RES0603")
      (libsource (lib "eagle-import") (part "RESISTOR-0603"))
    )
    (comp (ref "RFCON1")
      (value "RFCON-SMA-EDGE")
      (footprint "eagle-import:SMA-EDGE")
      (libsource (lib "eagle-import") (part "RFCON-SMA-EDGE"))
    )
    (comp (ref "U4")
      (value "MAX2671")
      (footprint "eagle-import:SOT23-6")
      (libsource (lib "eagle-import") (part "MAX2671"))
    )
    (comp (ref "U5")
      (value "2450BP15E0100")
      (footprint "eagle-import:2450BP15E0100")
      (libsource (lib "eagle-import") (part "2450BP15E0100"))
    )
    (comp (ref "C50")
      (value "100nF")
      (footprint "eagle-import:CAP0603")
      (libsource (lib "eagle-import") (part "CAPACITOR-0603"))
    )
    (comp (ref "C51")
      (value "4.7uF")
      (footprint "eagle-import:CAP0603")
      (fields (field (name "VOLTAGE") "35V"))
      (libsource (lib "eagle-import") (part "CAPACITOR-0603"))
    )
    (comp (ref "C52")
      (value "4.7uF")
      (footprint "eagle-import:CAP0603")
      (libsource (lib "eagle-import") (part "CAPACITOR-0603"))
    )
    (comp (ref "C53")
      (value "470pF")
      (footprint "eagle-import:CAP0603")
      (libsource (lib "eagle-import") (part "CAPACITOR-0603"))
    )
    (comp (ref "C54")
      (value "1uF")
      (footprint "eagle-import:CAP0603")
      (fields (field (name "VOLTAGE") "50V"))
      (libsource (lib "eagle-import") (part "CAPACITOR-0603"))
    )
    (comp (ref "C55")
      (value "470pF")
      (footprint "eagle-import:CAP0603")
      (libsource (lib "eagle-import") (part "CAPACITOR-0603"))
    )
    (comp (ref "C56")
      (value "1uF")
      (footprint "eagle-import:CAP0603")
      (fields (field (name "VOLTAGE") "50V"))
      (libsource (lib "eagle-import") (part "CAPACITOR-0603"))
    )
    (comp (ref "C57")
      (value "1uF")
      (footprint "eagle-import:CAP0603")
      (libsource (lib "eagle-import") (part "CAPACITOR-0603"))
    )
    (comp (ref "C58")
      (value "10nF")
      (footprint "eagle-import:CAP0603")
      (libsource (lib "eagle-import") (part "CAPACITOR-0603"))
    )
    (comp (ref "C59")
      (value "470pF")
      (footprint "eagle-import:CAP0603")
      (libsource (lib "eagle-import") (part "CAPACITOR-0603"))
    )
    (comp (ref "C60")
      (value "100nF")
      (footprint "eagle-import:CAP0603")
      (libsource (lib "eagle-import") (part "CAPACITOR-0603"))
    )
    (comp (ref "C61")
      (value "100nF")
      (footprint "eagle-import:CAP0603")
      (libsource (lib "eagle-import") (part "CAPACITOR-0603"))
    )
    (comp (ref "C62")
      (value "10pF")
      (footprint "eagle-import:CAP0603")
      (libsource (lib "eagle-import") (part "CAPACITOR-0603"))
    )
    (comp (ref "C63")
      (value "470pF")
      (footprint "eagle-import:CAP0603")
      (libsource (lib "eagle-import") (part "CAPACITOR-0603"))
    )
    (comp (ref "C64")
      (value "100uF")
      (footprint "eagle-import:CAP1206")
      (libsource (lib "eagle-import") (part "CAPACITOR-1206"))
    )
    (comp (ref "C65")
      (value "100uF")
      (footprint "eagle-import:CAP1206")
      (libsource (lib "eagle-import") (part "CAPACITOR-1206"))
    )
    (comp (ref "C66")
      (value "100nF")
      (footprint "eagle-import:CAP0603")
      (libsource (lib "eagle-import") (part "CAPACITOR-0603"))
    )
    (comp (ref "C67")
      (value "1uF")
      (footprint "eagle-import:CAP0603")
      (libsource (lib "eagle-import") (part "CAPACITOR-0603"))
    )
    (comp (ref "C68")
      (value "4.7uF")
      (footprint "eagle-import:CAP0603")
      (fields (field (name "VOLTAGE") "35V"))
      (libsource (lib "eagle-import") (part "CAPACITOR-0603"))
    )
    (comp (ref "C69")
      (value "22uF")
      (footprint "eagle-import:CAP1206")
      (fields (field (name "VOLTAGE") "25V"))
      (libsource (lib "eagle-import") (part "CAPACITOR-1206"))
    )
    (comp (ref "C70")
      (value "1uF")
      (footprint "eagle-import:CAP0603")
      (fields (field (name "VOLTAGE") "50V"))
      (libsource (lib "eagle-import") (part "CAPACITOR-0603"))
    )
    (comp (ref "C71")
      (value "100nF")
      (footprint "eagle-import:CAP0603")
      (libsource (lib "eagle-import") (part "CAPACITOR-0603"))
    )
    (comp (ref "C72")
      (value "1uF")
      (footprint "eagle-import:CAP0603")
      (fields (field (name "VOLTAGE") "50V"))
      (libsource (lib "eagle-import") (part "CAPACITOR-0603"))
    )
    (comp (ref "C73")
      (value "470pF")
      (footprint "eagle-import:CAP0603")
      (libsource (lib "eagle-import") (part "CAPACITOR-0603"))
    )
    (comp (ref "C74")
      (value "1uF")
      (footprint "eagle-import:CAP0603")
      (libsource (lib "eagle-import") (part "CAPACITOR-0603"))
    )
    (comp (ref "C75")
      (value "10nF")
      (footprint "eagle-import:CAP0603")
      (libsource (lib "eagle-import") (part "CAPACITOR-0603"))
    )
    (comp (ref "C76")
      (value "100nF")
      (footprint "eagle-import:CAP0603")
      (libsource (lib "eagle-import") (part "CAPACITOR-0603"))
    )
    (comp (ref "C77")
      (value "10pF")
      (footprint "eagle-import:CAP0603")
      (libsource (lib "eagle-import") (part "CAPACITOR-0603"))
    )
    (comp (ref "C78")
      (value "1uF")
      (footprint "eagle-import:CAP0603")
      (libsource (lib "eagle-import") (part "CAPACITOR-0603"))
    )
    (comp (ref "C79")
      (value "1uF")
      (footprint "eagle-import:CAP0603")
      (libsource (lib "eagle-import") (part "CAPACITOR-0603"))
    )
    (comp (ref "C80")
      (value "22uF")
      (footprint "eagle-import:CAP1206")
      (fields (field (name "VOLTAGE") "25V"))
      (libsource (lib "eagle-import") (part "CAPACITOR-1206"))
    )
    (comp (ref "C81")
      (value "1uF")
      (footprint "eagle-import:CAP0603")
      (libsource (lib "eagle-import") (part "CAPACITOR-0603"))
    )
    (comp (ref "C82")
      (value "1uF")
      (footprint "eagle-import:CAP0603")
      (libsource (lib "eagle-import") (part "CAPACITOR-0603"))
    )
    (comp (ref "C83")
      (value "22uF")
      (footprint "eagle-import:CAP1206")
      (fields (field (name "VOLTAGE") "25V"))
      (libsource (lib "eagle-import") (part "CAPACITOR-1206"))
    )
    (comp (ref "C84")
      (value "100nF")
      (footprint "eagle-import:CAP0603")
      (libsource (lib "eagle-import") (part "CAPACITOR-0603"))
    )
    (comp (ref "C85")
      (value "10uF")
      (footprint "eagle-import:CAP1206")
      (fields (field (name "VOLTAGE") "50V"))
      (libsource (lib "eagle-import") (part "CAPACITOR-1206"))
    )
    (comp (ref "CON1")
      (value "2EDG-2P")
      (footprint "eagle-import:2EDG-2P")
      (libsource (lib "eagle-import") (part "2EDG-2P"))
    )
    (comp (ref "D4")
      (value "LED0603")
      (footprint "eagle-import:0603")
      (fields (field (name "COLOR") "GREEN"))
      (libsource (lib "eagle-import") (part "LED0603"))
    )
    (comp (ref "D5")
      (value "SMAJ24A")
      (footprint "eagle-import:DO214AC")
      (fields (field (name "MF") "Littelfuse"))
      (libsource (lib "eagle-import") (part "SMAJA24"))
    )
    (comp (ref "F1")
      (value "2.6A Hold")
      (footprint "eagle-import:1206")
      (fields (field (name "HOLD") "3A") (field (name "TRIP") "6A"))
      (libsource (lib "eagle-import") (part "PTC1206"))
    )
    (comp (ref "L12")
      (value "2.2uH")
      (footprint "eagle-import:IND2520")
      (fields (field (name "CURRENT") "2.2A"))
      (libsource (lib "eagle-import") (part "INDUCTOR-2.5X2X1.2MM"))
    )
    (comp (ref "L13")
      (value "4.7uH")
      (footprint "eagle-import:IND0606")
      (fields (field (name "CURRENT") "3A"))
      (libsource (lib "eagle-import") (part "INDUCTOR-6X6MM"))
    )
    (comp (ref "L14")
      (value "4.7uH")
      (footprint "eagle-import:IND0606")
      (fields (field (name "CURRENT") "3A"))
      (libsource (lib "eagle-import") (part "INDUCTOR-6X6MM"))
    )
    (comp (ref "Q1")
      (value "AO3400")
      (footprint "eagle-import:SOT23")
      (libsource (lib "eagle-import") (part "AO3400"))
    )
    (comp (ref "Q2")
      (value "AO3401")
      (footprint "eagle-import:SOT23")
      (libsource (lib "eagle-import") (part "AO3401"))
    )
    (comp (ref "R16")
      (value "147K Ohms")
      (footprint "eagle-import:RES0603")
      (libsource (lib "eagle-import") (part "RESISTOR-0603"))
    )
    (comp (ref "R17")
      (value "21K Ohms")
      (footprint "eagle-import:RES0603")
      (libsource (lib "eagle-import") (part "RESISTOR-0603"))
    )
    (comp (ref "R18")
      (value "147K Ohms")
      (footprint "eagle-import:RES0603")
      (libsource (lib "eagle-import") (part "RESISTOR-0603"))
    )
    (comp (ref "R19")
      (value "21K Ohms")
      (footprint "eagle-import:RES0603")
      (libsource (lib "eagle-import") (part "RESISTOR-0603"))
    )
    (comp (ref "R20")
      (value "41.2K Ohms")
      (footprint "eagle-import:RES0603")
      (libsource (lib "eagle-import") (part "RESISTOR-0603"))
    )
    (comp (ref "R21")
      (value "100K Ohms")
      (footprint "eagle-import:RES0603")
      (libsource (lib "eagle-import") (part "RESISTOR-0603"))
    )
    (comp (ref "R23")
      (value "309K Ohms")
      (footprint "eagle-import:RES0603")
      (libsource (lib "eagle-import") (part "RESISTOR-0603"))
    )
    (comp (ref "R24")
      (value "71.5K Ohms")
      (footprint "eagle-import:RES0603")
      (libsource (lib "eagle-import") (part "RESISTOR-0603"))
    )
    (comp (ref "R25")
      (value "100K Ohms")
      (footprint "eagle-import:RES0603")
      (libsource (lib "eagle-import") (part "RESISTOR-0603"))
    )
    (comp (ref "R26")
      (value "100K Ohms")
      (footprint "eagle-import:RES0603")
      (libsource (lib "eagle-import") (part "RESISTOR-0603"))
    )
    (comp (ref "R27")
      (value "1M Ohms")
      (footprint "eagle-import:RES0603")
      (libsource (lib "eagle-import") (part "RESISTOR-0603"))
    )
    (comp (ref "R28")
      (value "226K Ohms")
      (footprint "eagle-import:RES0603")
      (libsource (lib "eagle-import") (part "RESISTOR-0603"))
    )
    (comp (ref "R29")
      (value "22 Ohms")
      (footprint "eagle-import:RES0603")
      (libsource (lib "eagle-import") (part "RESISTOR-0603"))
    )
    (comp (ref "R30")
      (value "510 Ohms")
      (footprint "eagle-import:RES0603")
      (libsource (lib "eagle-import") (part "RESISTOR-0603"))
    )
    (comp (ref "R31")
      (value "10K Ohms")
      (footprint "eagle-import:RES0603")
      (libsource (lib "eagle-import") (part "RESISTOR-0603"))
    )
    (comp (ref "R32")
      (value "10K Ohms")
      (footprint "eagle-import:RES0603")
      (libsource (lib "eagle-import") (part "RESISTOR-0603"))
    )
    (comp (ref "R33")
      (value "3.9K Ohms")
      (footprint "eagle-import:RES0603")
      (libsource (lib "eagle-import") (part "RESISTOR-0603"))
    )
    (comp (ref "R34")
      (value "100K Ohms")
      (footprint "eagle-import:RES0603")
      (libsource (lib "eagle-import") (part "RESISTOR-0603"))
    )
    (comp (ref "R35")
      (value "210K Ohms")
      (footprint "eagle-import:RES0603")
      (libsource (lib "eagle-import") (part "RESISTOR-0603"))
    )
    (comp (ref "R36")
      (value "64.9K Ohms")
      (footprint "eagle-import:RES0603")
      (libsource (lib "eagle-import") (part "RESISTOR-0603"))
    )
    (comp (ref "R37")
      (value "41.2K Ohms")
      (footprint "eagle-import:RES0603")
      (libsource (lib "eagle-import") (part "RESISTOR-0603"))
    )
    (comp (ref "R38")
      (value "100K Ohms")
      (footprint "eagle-import:RES0603")
      (libsource (lib "eagle-import") (part "RESISTOR-0603"))
    )
    (comp (ref "R39")
      (value "1M Ohms")
      (footprint "eagle-import:RES0603")
      (libsource (lib "eagle-import") (part "RESISTOR-0603"))
    )
    (comp (ref "R40")
      (value "86.6K Ohms")
      (footprint "eagle-import:RES0603")
      (libsource (lib "eagle-import") (part "RESISTOR-0603"))
    )
    (comp (ref "U9")
      (value "MIC23155")
      (footprint "eagle-import:DFN10")
      (libsource (lib "eagle-import") (part "MIC23155"))
    )
    (comp (ref "U10")
      (value "LT8636")
      (footprint "eagle-import:QFN20_ASYM_CORNER")
      (libsource (lib "eagle-import") (part "LT8636"))
    )
    (comp (ref "U11")
      (value "ADP3334")
      (footprint "eagle-import:LFCSP8_3X3")
      (libsource (lib "eagle-import") (part "ADP3334"))
    )
    (comp (ref "U12")
      (value "LT8636")
      (footprint "eagle-import:QFN20_ASYM_CORNER")
      (libsource (lib "eagle-import") (part "LT8636"))
    )
    (comp (ref "U13")
      (value "ADP150UJZ-3.3")
      (footprint "eagle-import:SOT23-5")
      (libsource (lib "eagle-import") (part "ADP150UJZ-3.3"))
    )
    (comp (ref "U14")
      (value "ADP150UJZ-3.3")
      (footprint "eagle-import:SOT23-5")
      (libsource (lib "eagle-import") (part "ADP150UJZ-3.3"))
    )
  )
  (nets
    (net (code "1") (name "1V8") (class "Default")
      (node (ref "C2") (pin "1") (pinfunction "C1_1") (pintype "passive"))
      (node (ref "L1") (pin "1") (pinfunction "1_1") (pintype "passive"))
      (node (ref "U1") (pin "28") (pinfunction "DVDD_28") (pintype "bidirectional"))
    )
    (net (code "2") (name "3V3") (class "Default")
      (node (ref "C1") (pin "1") (pinfunction "C1_1") (pintype "passive"))
      (node (ref "C60") (pin "1") (pinfunction "C1_1") (pintype "passive"))
      (node (ref "C64") (pin "1") (pinfunction "C1_1") (pintype "passive"))
      (node (ref "C8") (pin "1") (pinfunction "C1_1") (pintype "passive"))
      (node (ref "C86") (pin "1") (pinfunction "C1_1") (pintype "passive"))
      (node (ref "C87") (pin "1") (pinfunction "C1_1") (pintype "passive"))
      (node (ref "JP1") (pin "1") (pinfunction "S_1") (pintype "passive"))
      (node (ref "L12") (pin "2") (pinfunction "2_2") (pintype "passive"))
      (node (ref "R1") (pin "2") (pinfunction "2_2") (pintype "passive"))
      (node (ref "R21") (pin "2") (pinfunction "2_2") (pintype "passive"))
      (node (ref "R23") (pin "2") (pinfunction "2_2") (pintype "passive"))
      (node (ref "R34") (pin "2") (pinfunction "2_2") (pintype "passive"))
      (node (ref "R38") (pin "2") (pinfunction "2_2") (pintype "passive"))
      (node (ref "TC1") (pin "1") (pinfunction "S_1") (pintype "passive"))
      (node (ref "U1") (pin "22") (pinfunction "AVDD_22") (pintype "bidirectional"))
      (node (ref "U1") (pin "27") (pinfunction "VREGVDD_27") (pintype "bidirectional"))
      (node (ref "U1") (pin "30") (pinfunction "IOVDD0_30") (pintype "bidirectional"))
      (node (ref "U1") (pin "5") (pinfunction "AVDD_5") (pintype "bidirectional"))
      (node (ref "U3") (pin "28") (pinfunction "DVDD_28") (pintype "bidirectional"))
      (node (ref "U9") (pin "3") (pinfunction "SNS_3") (pintype "bidirectional"))
    )
    (net (code "3") (name "3V3_ANA_MIXER_CLEAN") (class "Default")
      (node (ref "C24") (pin "1") (pinfunction "C1_1") (pintype "passive"))
      (node (ref "C25") (pin "1") (pinfunction "C1_1") (pintype "passive"))
      (node (ref "C26") (pin "1") (pinfunction "C1_1") (pintype "passive"))
      (node (ref "C27") (pin "1") (pinfunction "C1_1") (pintype "passive"))
      (node (ref "C81") (pin "1") (pinfunction "C1_1") (pintype "passive"))
      (node (ref "L6") (pin "2") (pinfunction "2_2") (pintype "passive"))
      (node (ref "U13") (pin "5") (pinfunction "OUT_5") (pintype "bidirectional"))
      (node (ref "U4") (pin "5") (pinfunction "VCC_5") (pintype "bidirectional"))
    )
    (net (code "4") (name "3V3_ANA_PLL_CLEAN") (class "Default")
      (node (ref "C4") (pin "1") (pinfunction "C1_1") (pintype "passive"))
      (node (ref "C5") (pin "1") (pinfunction "C1_1") (pintype "passive"))
      (node (ref "C6") (pin "1") (pinfunction "C1_1") (pintype "passive"))
      (node (ref "C7") (pin "1") (pinfunction "C1_1") (pintype "passive"))
      (node (ref "C82") (pin "1") (pinfunction "C1_1") (pintype "passive"))
      (node (ref "L2") (pin "1") (pinfunction "1_1") (pintype "passive"))
      (node (ref "L3") (pin "2") (pinfunction "2_2") (pintype "passive"))
      (node (ref "U14") (pin "5") (pinfunction "OUT_5") (pintype "bidirectional"))
      (node (ref "U2") (pin "4") (pinfunction "VDD_4") (pintype "power_in"))
      (node (ref "U3") (pin "10") (pinfunction "AVDD_10") (pintype "bidirectional"))
      (node (ref "U3") (pin "16") (pinfunction "VVCO_16") (pintype "bidirectional"))
      (node (ref "U3") (pin "17") (pinfunction "VVCO_17") (pintype "bidirectional"))
      (node (ref "U3") (pin "32") (pinfunction "SDVDD_32") (pintype "bidirectional"))
      (node (ref "U3") (pin "6") (pinfunction "VP_6") (pintype "bidirectional"))
    )
    (net (code "5") (name "5V0") (class "Default")
      (node (ref "C50") (pin "1") (pinfunction "C1_1") (pintype "passive"))
      (node (ref "C52") (pin "1") (pinfunction "C1_1") (pintype "passive"))
      (node (ref "C62") (pin "1") (pinfunction "C1_1") (pintype "passive"))
      (node (ref "C65") (pin "1") (pinfunction "C1_1") (pintype "passive"))
      (node (ref "C66") (pin "1") (pinfunction "C1_1") (pintype "passive"))
      (node (ref "C67") (pin "1") (pinfunction "C1_1") (pintype "passive"))
      (node (ref "C78") (pin "1") (pinfunction "C1_1") (pintype "passive"))
      (node (ref "C79") (pin "1") (pinfunction "C1_1") (pintype "passive"))
      (node (ref "L13") (pin "2") (pinfunction "2_2") (pintype "passive"))
      (node (ref "R25") (pin "2") (pinfunction "2_2") (pintype "passive"))
      (node (ref "R27") (pin "2") (pinfunction "2_2") (pintype "passive"))
      (node (ref "R30") (pin "2") (pinfunction "2_2") (pintype "passive"))
      (node (ref "U10") (pin "2") (pinfunction "BIAS_2") (pintype "bidirectional"))
      (node (ref "U11") (pin "7") (pinfunction "IN_7") (pintype "bidirectional"))
      (node (ref "U11") (pin "8") (pinfunction "IN_8") (pintype "bidirectional"))
      (node (ref "U11") (pin "9") (pinfunction "IN_9") (pintype "bidirectional"))
      (node (ref "U13") (pin "1") (pinfunction "VIN_1") (pintype "bidirectional"))
      (node (ref "U13") (pin "3") (pinfunction "EN_3") (pintype "bidirectional"))
      (node (ref "U14") (pin "1") (pinfunction "VIN_1") (pintype "bidirectional"))
      (node (ref "U14") (pin "3") (pinfunction "EN_3") (pintype "bidirectional"))
      (node (ref "U9") (pin "2") (pinfunction "EN_2") (pintype "bidirectional"))
      (node (ref "U9") (pin "8") (pinfunction "VIN_8") (pintype "bidirectional"))
      (node (ref "U9") (pin "9") (pinfunction "VIN_9") (pintype "bidirectional"))
    )
    (net (code "6") (name "5V0_ANA_PA_CLEAN") (class "Default")
      (node (ref "C31") (pin "1") (pinfunction "C1_1") (pintype "passive"))
      (node (ref "C32") (pin "1") (pinfunction "C1_1") (pintype "passive"))
      (node (ref "C33") (pin "1") (pinfunction "C1_1") (pintype "passive"))
      (node (ref "C34") (pin "1") (pinfunction "C1_1") (pintype "passive"))
      (node (ref "C36") (pin "1") (pinfunction "C1_1") (pintype "passive"))
      (node (ref "C37") (pin "1") (pinfunction "C1_1") (pintype "passive"))
      (node (ref "C38") (pin "1") (pinfunction "C1_1") (pintype "passive"))
      (node (ref "C73") (pin "1") (pinfunction "C1_1") (pintype "passive"))
      (node (ref "L10") (pin "2") (pinfunction "2_2") (pintype "passive"))
      (node (ref "L9") (pin "2") (pinfunction "2_2") (pintype "passive"))
      (node (ref "R14") (pin "2") (pinfunction "2_2") (pintype "passive"))
      (node (ref "R35") (pin "2") (pinfunction "2_2") (pintype "passive"))
      (node (ref "U11") (pin "1") (pinfunction "OUT_1") (pintype "bidirectional"))
      (node (ref "U11") (pin "2") (pinfunction "OUT_2") (pintype "bidirectional"))
    )
    (net (code "7") (name "5V0_PGOOD") (class "Default")
      (node (ref "R21") (pin "1") (pinfunction "1_1") (pintype "passive"))
      (node (ref "U1") (pin "23") (pinfunction "PB14_23") (pintype "bidirectional"))
      (node (ref "U10") (pin "1") (pinfunction "PG_1") (pintype "bidirectional"))
    )
    (net (code "8") (name "5V0_VSENSE") (class "Default")
      (node (ref "C63") (pin "1") (pinfunction "C1_1") (pintype "passive"))
      (node (ref "R25") (pin "1") (pinfunction "1_1") (pintype "passive"))
      (node (ref "R26") (pin "2") (pinfunction "2_2") (pintype "passive"))
      (node (ref "U1") (pin "19") (pinfunction "PB11_19") (pintype "bidirectional"))
    )
    (net (code "9") (name "12V0") (class "Default")
      (node (ref "C77") (pin "1") (pinfunction "C1_1") (pintype "passive"))
      (node (ref "C80") (pin "1") (pinfunction "C1_1") (pintype "passive"))
      (node (ref "C83") (pin "1") (pinfunction "C1_1") (pintype "passive"))
      (node (ref "C84") (pin "1") (pinfunction "C1_1") (pintype "passive"))
      (node (ref "L14") (pin "2") (pinfunction "2_2") (pintype "passive"))
      (node (ref "Q2") (pin "2") (pinfunction "S_2") (pintype "passive"))
      (node (ref "R18") (pin "2") (pinfunction "2_2") (pintype "passive"))
      (node (ref "R32") (pin "2") (pinfunction "2_2") (pintype "passive"))
      (node (ref "R39") (pin "2") (pinfunction "2_2") (pintype "passive"))
      (node (ref "U12") (pin "2") (pinfunction "BIAS_2") (pintype "bidirectional"))
    )
    (net (code "10") (name "12V0_ANA_PA_CLEAN") (class "Default")
      (node (ref "C41") (pin "1") (pinfunction "C1_1") (pintype "passive"))
      (node (ref "C42") (pin "1") (pinfunction "C1_1") (pintype "passive"))
      (node (ref "C69") (pin "1") (pinfunction "C1_1") (pintype "passive"))
      (node (ref "C71") (pin "1") (pinfunction "C1_1") (pintype "passive"))
      (node (ref "L11") (pin "2") (pinfunction "2_2") (pintype "passive"))
      (node (ref "Q2") (pin "3") (pinfunction "D_3") (pintype "passive"))
      (node (ref "R15") (pin "2") (pinfunction "2_2") (pintype "passive"))
    )
    (net (code "11") (name "12V0_PA_BIAS_EN") (class "Default")
      (node (ref "R29") (pin "2") (pinfunction "2_2") (pintype "passive"))
      (node (ref "U1") (pin "18") (pinfunction "PA1_18") (pintype "bidirectional"))
    )
    (net (code "12") (name "12V0_PGOOD") (class "Default")
      (node (ref "R38") (pin "1") (pinfunction "1_1") (pintype "passive"))
      (node (ref "U1") (pin "24") (pinfunction "PB15_24") (pintype "bidirectional"))
      (node (ref "U12") (pin "1") (pinfunction "PG_1") (pintype "bidirectional"))
    )
    (net (code "13") (name "12V0_VSENSE") (class "Default")
      (node (ref "C59") (pin "1") (pinfunction "C1_1") (pintype "passive"))
      (node (ref "R18") (pin "1") (pinfunction "1_1") (pintype "passive"))
      (node (ref "R19") (pin "2") (pinfunction "2_2") (pintype "passive"))
      (node (ref "U1") (pin "20") (pinfunction "PB12_20") (pintype "bidirectional"))
    )
    (net (code "14") (name "GND") (class "Default")
      (node (ref "C1") (pin "2") (pinfunction "C2_2") (pintype "passive"))
      (node (ref "C10") (pin "2") (pinfunction "C2_2") (pintype "passive"))
      (node (ref "C11") (pin "2") (pinfunction "C2_2") (pintype "passive"))
      (node (ref "C12") (pin "2") (pinfunction "C2_2") (pintype "passive"))
      (node (ref "C13") (pin "2") (pinfunction "C2_2") (pintype "passive"))
      (node (ref "C14") (pin "2") (pinfunction "C2_2") (pintype "passive"))
      (node (ref "C15") (pin "2") (pinfunction "C2_2") (pintype "passive"))
      (node (ref "C17") (pin "2") (pinfunction "C2_2") (pintype "passive"))
      (node (ref "C2") (pin "2") (pinfunction "C2_2") (pintype "passive"))
      (node (ref "C20") (pin "2") (pinfunction "C2_2") (pintype "passive"))
      (node (ref "C21") (pin "2") (pinfunction "C2_2") (pintype "passive"))
      (node (ref "C22") (pin "2") (pinfunction "C2_2") (pintype "passive"))
      (node (ref "C24") (pin "2") (pinfunction "C2_2") (pintype "passive"))
      (node (ref "C25") (pin "2") (pinfunction "C2_2") (pintype "passive"))
      (node (ref "C26") (pin "2") (pinfunction "C2_2") (pintype "passive"))
      (node (ref "C27") (pin "2") (pinfunction "C2_2") (pintype "passive"))
      (node (ref "C29") (pin "2") (pinfunction "C2_2") (pintype "passive"))
      (node (ref "C3") (pin "2") (pinfunction "C2_2") (pintype "passive"))
      (node (ref "C31") (pin "2") (pinfunction "C2_2") (pintype "passive"))
      (node (ref "C32") (pin "2") (pinfunction "C2_2") (pintype "passive"))
      (node (ref "C33") (pin "2") (pinfunction "C2_2") (pintype "passive"))
      (node (ref "C34") (pin "2") (pinfunction "C2_2") (pintype "passive"))
      (node (ref "C36") (pin "2") (pinfunction "C2_2") (pintype "passive"))
      (node (ref "C37") (pin "2") (pinfunction "C2_2") (pintype "passive"))
      (node (ref "C38") (pin "2") (pinfunction "C2_2") (pintype "passive"))
      (node (ref "C4") (pin "2") (pinfunction "C2_2") (pintype "passive"))
      (node (ref "C40") (pin "2") (pinfunction "C2_2") (pintype "passive"))
      (node (ref "C41") (pin "2") (pinfunction "C2_2") (pintype "passive"))
      (node (ref "C42") (pin "2") (pinfunction "C2_2") (pintype "passive"))
      (node (ref "C43") (pin "2") (pinfunction "C2_2") (pintype "passive"))
      (node (ref "C44") (pin "2") (pinfunction "C2_2") (pintype "passive"))
      (node (ref "C46") (pin "2") (pinfunction "C2_2") (pintype "passive"))
      (node (ref "C47") (pin "2") (pinfunction "C2_2") (pintype "passive"))
      (node (ref "C48") (pin "2") (pinfunction "C2_2") (pintype "passive"))
      (node (ref "C49") (pin "2") (pinfunction "C2_2") (pintype "passive"))
      (node (ref "C5") (pin "2") (pinfunction "C2_2") (pintype "passive"))
      (node (ref "C50") (pin "2") (pinfunction "C2_2") (pintype "passive"))
      (node (ref "C51") (pin "2") (pinfunction "C2_2") (pintype "passive"))
      (node (ref "C52") (pin "2") (pinfunction "C2_2") (pintype "passive"))
      (node (ref "C53") (pin "2") (pinfunction "C2_2") (pintype "passive"))
      (node (ref "C54") (pin "2") (pinfunction "C2_2") (pintype "passive"))
      (node (ref "C55") (pin "2") (pinfunction "C2_2") (pintype "passive"))
      (node (ref "C56") (pin "2") (pinfunction "C2_2") (pintype "passive"))
      (node (ref "C57") (pin "2") (pinfunction "C2_2") (pintype "passive"))
      (node (ref "C58") (pin "2") (pinfunction "C2_2") (pintype "passive"))
      (node (ref "C59") (pin "2") (pinfunction "C2_2") (pintype "passive"))
      (node (ref "C6") (pin "2") (pinfunction "C2_2") (pintype "passive"))
      (node (ref "C60") (pin "2") (pinfunction "C2_2") (pintype "passive"))
      (node (ref "C63") (pin "2") (pinfunction "C2_2") (pintype "passive"))
      (node (ref "C64") (pin "2") (pinfunction "C2_2") (pintype "passive"))
      (node (ref "C65") (pin "2") (pinfunction "C2_2") (pintype "passive"))
      (node (ref "C66") (pin "2") (pinfunction "C2_2") (pintype "passive"))
      (node (ref "C67") (pin "2") (pinfunction "C2_2") (pintype "passive"))
      (node (ref "C68") (pin "2") (pinfunction "C2_2") (pintype "passive"))
      (node (ref "C69") (pin "2") (pinfunction "C2_2") (pintype "passive"))
      (node (ref "C7") (pin "2") (pinfunction "C2_2") (pintype "passive"))
      (node (ref "C70") (pin "2") (pinfunction "C2_2") (pintype "passive"))
      (node (ref "C71") (pin "2") (pinfunction "C2_2") (pintype "passive"))
      (node (ref "C72") (pin "2") (pinfunction "C2_2") (pintype "passive"))
      (node (ref "C74") (pin "2") (pinfunction "C2_2") (pintype "passive"))
      (node (ref "C75") (pin "2") (pinfunction "C2_2") (pintype "passive"))
      (node (ref "C78") (pin "2") (pinfunction "C2_2") (pintype "passive"))
      (node (ref "C79") (pin "2") (pinfunction "C2_2") (pintype "passive"))
      (node (ref "C8") (pin "2") (pinfunction "C2_2") (pintype "passive"))
      (node (ref "C80") (pin "2") (pinfunction "C2_2") (pintype "passive"))
      (node (ref "C81") (pin "2") (pinfunction "C2_2") (pintype "passive"))
      (node (ref "C82") (pin "2") (pinfunction "C2_2") (pintype "passive"))
      (node (ref "C83") (pin "2") (pinfunction "C2_2") (pintype "passive"))
      (node (ref "C84") (pin "2") (pinfunction "C2_2") (pintype "passive"))
      (node (ref "C85") (pin "2") (pinfunction "C2_2") (pintype "passive"))
      (node (ref "C86") (pin "2") (pinfunction "C2_2") (pintype "passive"))
      (node (ref "C87") (pin "2") (pinfunction "C2_2") (pintype "passive"))
      (node (ref "C88") (pin "2") (pinfunction "C2_2") (pintype "passive"))
      (node (ref "CON1") (pin "P$1") (pinfunction "S_P$1") (pintype "passive"))
      (node (ref "D1") (pin "C") (pinfunction "C_C") (pintype "passive"))
      (node (ref "D2") (pin "C") (pinfunction "C_C") (pintype "passive"))
      (node (ref "D3") (pin "C") (pinfunction "C_C") (pintype "passive"))
      (node (ref "D4") (pin "C") (pinfunction "C_C") (pintype "passive"))
      (node (ref "D5") (pin "A") (pinfunction "A_A") (pintype "passive"))
      (node (ref "JP1") (pin "3") (pinfunction "S_3") (pintype "passive"))
      (node (ref "L7") (pin "2") (pinfunction "2_2") (pintype "passive"))
      (node (ref "L8") (pin "2") (pinfunction "2_2") (pintype "passive"))
      (node (ref "Q1") (pin "2") (pinfunction "S_2") (pintype "passive"))
      (node (ref "R10") (pin "1") (pinfunction "1_1") (pintype "passive"))
      (node (ref "R11") (pin "1") (pinfunction "1_1") (pintype "passive"))
      (node (ref "R13") (pin "1") (pinfunction "1_1") (pintype "passive"))
      (node (ref "R17") (pin "1") (pinfunction "1_1") (pintype "passive"))
      (node (ref "R19") (pin "1") (pinfunction "1_1") (pintype "passive"))
      (node (ref "R20") (pin "1") (pinfunction "1_1") (pintype "passive"))
      (node (ref "R24") (pin "1") (pinfunction "1_1") (pintype "passive"))
      (node (ref "R26") (pin "1") (pinfunction "1_1") (pintype "passive"))
      (node (ref "R28") (pin "1") (pinfunction "1_1") (pintype "passive"))
      (node (ref "R3") (pin "1") (pinfunction "1_1") (pintype "passive"))
      (node (ref "R31") (pin "1") (pinfunction "1_1") (pintype "passive"))
      (node (ref "R36") (pin "1") (pinfunction "1_1") (pintype "passive"))
      (node (ref "R37") (pin "1") (pinfunction "1_1") (pintype "passive"))
      (node (ref "R4") (pin "1") (pinfunction "1_1") (pintype "passive"))
      (node (ref "R40") (pin "1") (pinfunction "1_1") (pintype "passive"))
      (node (ref "R41") (pin "1") (pinfunction "1_1") (pintype "passive"))
      (node (ref "R5") (pin "1") (pinfunction "1_1") (pintype "passive"))
      (node (ref "R7") (pin "1") (pinfunction "1_1") (pintype "passive"))
      (node (ref "RFCON1") (pin "GND@0") (pinfunction "GND_GND@0") (pintype "bidirectional"))
      (node (ref "RFCON1") (pin "GND@1") (pinfunction "GND_GND@1") (pintype "bidirectional"))
      (node (ref "RFCON1") (pin "GND@2") (pinfunction "GND_GND@2") (pintype "bidirectional"))
      (node (ref "RFCON1") (pin "GND@3") (pinfunction "GND_GND@3") (pintype "bidirectional"))
      (node (ref "RFCON2") (pin "GND@0") (pinfunction "GND_GND@0") (pintype "bidirectional"))
      (node (ref "RFCON2") (pin "GND@1") (pinfunction "GND_GND@1") (pintype "bidirectional"))
      (node (ref "RFCON2") (pin "GND@2") (pinfunction "GND_GND@2") (pintype "bidirectional"))
      (node (ref "RFCON2") (pin "GND@3") (pinfunction "GND_GND@3") (pintype "bidirectional"))
      (node (ref "TC1") (pin "3") (pinfunction "S_3") (pintype "passive"))
      (node (ref "U1") (pin "25") (pinfunction "VREGVSS_25") (pintype "bidirectional"))
      (node (ref "U1") (pin "33") (pinfunction "VSS_33") (pintype "bidirectional"))
      (node (ref "U10") (pin "12") (pinfunction "GND_12") (pintype "bidirectional"))
      (node (ref "U10") (pin "13") (pinfunction "GND_13") (pintype "bidirectional"))
      (node (ref "U10") (pin "21") (pinfunction "GND_21") (pintype "bidirectional"))
      (node (ref "U10") (pin "4") (pinfunction "GND_4") (pintype "bidirectional"))
      (node (ref "U10") (pin "5") (pinfunction "GND_5") (pintype "bidirectional"))
      (node (ref "U10") (pin "M1") (pinfunction "GND_M1") (pintype "bidirectional"))
      (node (ref "U10") (pin "M2") (pinfunction "GND_M2") (pintype "bidirectional"))
      (node (ref "U10") (pin "M3") (pinfunction "GND_M3") (pintype "bidirectional"))
      (node (ref "U10") (pin "M4") (pinfunction "GND_M4") (pintype "bidirectional"))
      (node (ref "U11") (pin "5") (pinfunction "GND_5") (pintype "bidirectional"))
      (node (ref "U12") (pin "12") (pinfunction "GND_12") (pintype "bidirectional"))
      (node (ref "U12") (pin "13") (pinfunction "GND_13") (pintype "bidirectional"))
      (node (ref "U12") (pin "21") (pinfunction "GND_21") (pintype "bidirectional"))
      (node (ref "U12") (pin "4") (pinfunction "GND_4") (pintype "bidirectional"))
      (node (ref "U12") (pin "5") (pinfunction "GND_5") (pintype "bidirectional"))
      (node (ref "U12") (pin "M1") (pinfunction "GND_M1") (pintype "bidirectional"))
      (node (ref "U12") (pin "M2") (pinfunction "GND_M2") (pintype "bidirectional"))
      (node (ref "U12") (pin "M3") (pinfunction "GND_M3") (pintype "bidirectional"))
      (node (ref "U12") (pin "M4") (pinfunction "GND_M4") (pintype "bidirectional"))
      (node (ref "U13") (pin "2") (pinfunction "GND_2") (pintype "bidirectional"))
      (node (ref "U14") (pin "2") (pinfunction "GND_2") (pintype "bidirectional"))
      (node (ref "U2") (pin "1") (pinfunction "GND_1") (pintype "power_in"))
      (node (ref "U2") (pin "2") (pinfunction "GND_2") (pintype "power_in"))
      (node (ref "U3") (pin "11") (pinfunction "AGNDVCO_11") (pintype "bidirectional"))
      (node (ref "U3") (pin "18") (pinfunction "AGNDVCO_18") (pintype "bidirectional"))
      (node (ref "U3") (pin "21") (pinfunction "AGNDVCO_21") (pintype "bidirectional"))
      (node (ref "U3") (pin "27") (pinfunction "DGND_27") (pintype "bidirectional"))
      (node (ref "U3") (pin "31") (pinfunction "SDGND_31") (pintype "bidirectional"))
      (node (ref "U3") (pin "33") (pinfunction "GND_33") (pintype "bidirectional"))
      (node (ref "U3") (pin "8") (pinfunction "CPGND_8") (pintype "bidirectional"))
      (node (ref "U3") (pin "9") (pinfunction "AGND_9") (pintype "bidirectional"))
      (node (ref "U4") (pin "2") (pinfunction "GND_2") (pintype "bidirectional"))
      (node (ref "U5") (pin "1") (pinfunction "GND_1") (pintype "bidirectional"))
      (node (ref "U5") (pin "3") (pinfunction "GND_3") (pintype "bidirectional"))
      (node (ref "U6") (pin "2") (pinfunction "GND_2") (pintype "bidirectional"))
      (node (ref "U6") (pin "4") (pinfunction "GND_4") (pintype "bidirectional"))
      (node (ref "U7") (pin "2") (pinfunction "GND_2") (pintype "bidirectional"))
      (node (ref "U7") (pin "4") (pinfunction "GND_4") (pintype "bidirectional"))
      (node (ref "U8") (pin "1") (pinfunction "GND_1") (pintype "bidirectional"))
      (node (ref "U8") (pin "16") (pinfunction "GND_16") (pintype "bidirectional"))
      (node (ref "U8") (pin "17") (pinfunction "GND_17") (pintype "bidirectional"))
      (node (ref "U8") (pin "20") (pinfunction "GND_20") (pintype "bidirectional"))
      (node (ref "U8") (pin "22") (pinfunction "GND_22") (pintype "bidirectional"))
      (node (ref "U8") (pin "24") (pinfunction "GND_24") (pintype "bidirectional"))
      (node (ref "U8") (pin "25") (pinfunction "GND_25") (pintype "bidirectional"))
      (node (ref "U8") (pin "32") (pinfunction "GND_32") (pintype "bidirectional"))
      (node (ref "U8") (pin "33") (pinfunction "GND_33") (pintype "bidirectional"))
      (node (ref "U8") (pin "4") (pinfunction "GND_4") (pintype "bidirectional"))
      (node (ref "U8") (pin "6") (pinfunction "GND_6") (pintype "bidirectional"))
      (node (ref "U8") (pin "8") (pinfunction "GND_8") (pintype "bidirectional"))
      (node (ref "U8") (pin "9") (pinfunction "GND_9") (pintype "bidirectional"))
      (node (ref "U9") (pin "10") (pinfunction "PGND_10") (pintype "bidirectional"))
      (node (ref "U9") (pin "11") (pinfunction "PGND_11") (pintype "bidirectional"))
      (node (ref "U9") (pin "7") (pinfunction "AGND_7") (pintype "bidirectional"))
    )
    (net (code "15") (name "IF_FREQ_SEL") (class "Default")
      (node (ref "C88") (pin "1") (pinfunction "C1_1") (pintype "passive"))
      (node (ref "JP1") (pin "2") (pinfunction "S_2") (pintype "passive"))
      (node (ref "R41") (pin "2") (pinfunction "2_2") (pintype "passive"))
      (node (ref "U1") (pin "32") (pinfunction "PC11_32") (pintype "bidirectional"))
    )
    (net (code "16") (name "LED") (class "Default")
      (node (ref "R2") (pin "2") (pinfunction "2_2") (pintype "passive"))
      (node (ref "U1") (pin "31") (pinfunction "PC10_31") (pintype "bidirectional"))
    )
    (net (code "17") (name "MIXER_LO") (class "Default")
      (node (ref "C18") (pin "2") (pinfunction "C2_2") (pintype "passive"))
      (node (ref "U4") (pin "1") (pinfunction "LO_1") (pintype "bidirectional"))
    )
    (net (code "18") (name "Net-(C3-C1)") (class "Default")
      (node (ref "C3") (pin "1") (pinfunction "C1_1") (pintype "passive"))
      (node (ref "U1") (pin "29") (pinfunction "DECOUPLE_29") (pintype "bidirectional"))
    )
    (net (code "19") (name "Net-(C9-C1)") (class "Default")
      (node (ref "C9") (pin "1") (pinfunction "C1_1") (pintype "passive"))
      (node (ref "U2") (pin "3") (pinfunction "CLK_3") (pintype "output"))
    )
    (net (code "20") (name "Net-(C9-C2)") (class "Default")
      (node (ref "C9") (pin "2") (pinfunction "C2_2") (pintype "passive"))
      (node (ref "U3") (pin "29") (pinfunction "REFIN_29") (pintype "bidirectional"))
    )
    (net (code "21") (name "Net-(C10-C1)") (class "Default")
      (node (ref "C10") (pin "1") (pinfunction "C1_1") (pintype "passive"))
      (node (ref "C11") (pin "1") (pinfunction "C1_1") (pintype "passive"))
      (node (ref "U3") (pin "24") (pinfunction "VREF_24") (pintype "bidirectional"))
    )
    (net (code "22") (name "Net-(C12-C1)") (class "Default")
      (node (ref "C12") (pin "1") (pinfunction "C1_1") (pintype "passive"))
      (node (ref "C13") (pin "1") (pinfunction "C1_1") (pintype "passive"))
      (node (ref "U3") (pin "23") (pinfunction "VCOM_23") (pintype "bidirectional"))
    )
    (net (code "23") (name "Net-(C14-C1)") (class "Default")
      (node (ref "C14") (pin "1") (pinfunction "C1_1") (pintype "passive"))
      (node (ref "C15") (pin "1") (pinfunction "C1_1") (pintype "passive"))
      (node (ref "U3") (pin "19") (pinfunction "TEMP_19") (pintype "bidirectional"))
    )
    (net (code "24") (name "Net-(C16-C1)") (class "Default")
      (node (ref "C16") (pin "1") (pinfunction "C1_1") (pintype "passive"))
      (node (ref "L2") (pin "2") (pinfunction "2_2") (pintype "passive"))
      (node (ref "U3") (pin "12") (pinfunction "RFOUTA+_12") (pintype "bidirectional"))
    )
    (net (code "25") (name "Net-(C16-C2)") (class "Default")
      (node (ref "C16") (pin "2") (pinfunction "C2_2") (pintype "passive"))
      (node (ref "C18") (pin "1") (pinfunction "C1_1") (pintype "passive"))
      (node (ref "L4") (pin "1") (pinfunction "1_1") (pintype "passive"))
    )
    (net (code "26") (name "Net-(C17-C1)") (class "Default")
      (node (ref "C17") (pin "1") (pinfunction "C1_1") (pintype "passive"))
      (node (ref "L3") (pin "1") (pinfunction "1_1") (pintype "passive"))
      (node (ref "L4") (pin "2") (pinfunction "2_2") (pintype "passive"))
      (node (ref "U3") (pin "13") (pinfunction "RFOUTA-_13") (pintype "bidirectional"))
    )
    (net (code "27") (name "Net-(C19-C1)") (class "Default")
      (node (ref "C19") (pin "1") (pinfunction "C1_1") (pintype "passive"))
      (node (ref "C20") (pin "1") (pinfunction "C1_1") (pintype "passive"))
      (node (ref "R8") (pin "2") (pinfunction "2_2") (pintype "passive"))
      (node (ref "U3") (pin "7") (pinfunction "CPOUT_7") (pintype "bidirectional"))
    )
    (net (code "28") (name "Net-(C19-C2)") (class "Default")
      (node (ref "C19") (pin "2") (pinfunction "C2_2") (pintype "passive"))
      (node (ref "R6") (pin "1") (pinfunction "1_1") (pintype "passive"))
      (node (ref "R7") (pin "2") (pinfunction "2_2") (pintype "passive"))
    )
    (net (code "29") (name "Net-(C21-C1)") (class "Default")
      (node (ref "C21") (pin "1") (pinfunction "C1_1") (pintype "passive"))
      (node (ref "R8") (pin "1") (pinfunction "1_1") (pintype "passive"))
      (node (ref "U3") (pin "20") (pinfunction "VTUNE_20") (pintype "bidirectional"))
    )
    (net (code "30") (name "Net-(C22-C1)") (class "Default")
      (node (ref "C22") (pin "1") (pinfunction "C1_1") (pintype "passive"))
      (node (ref "R10") (pin "2") (pinfunction "2_2") (pintype "passive"))
      (node (ref "R9") (pin "1") (pinfunction "1_1") (pintype "passive"))
      (node (ref "U4") (pin "6") (pinfunction "~{SHDN}_6") (pintype "bidirectional"))
    )
    (net (code "31") (name "Net-(C23-C1)") (class "Default")
      (node (ref "C23") (pin "1") (pinfunction "C1_1") (pintype "passive"))
      (node (ref "RFCON1") (pin "SIG") (pinfunction "SIGNAL_SIG") (pintype "bidirectional"))
    )
    (net (code "32") (name "Net-(C23-C2)") (class "Default")
      (node (ref "C23") (pin "2") (pinfunction "C2_2") (pintype "passive"))
      (node (ref "R11") (pin "2") (pinfunction "2_2") (pintype "passive"))
      (node (ref "R12") (pin "2") (pinfunction "2_2") (pintype "passive"))
    )
    (net (code "33") (name "Net-(C28-C1)") (class "Default")
      (node (ref "C28") (pin "1") (pinfunction "C1_1") (pintype "passive"))
      (node (ref "L5") (pin "2") (pinfunction "2_2") (pintype "passive"))
      (node (ref "L6") (pin "1") (pinfunction "1_1") (pintype "passive"))
    )
    (net (code "34") (name "Net-(C28-C2)") (class "Default")
      (node (ref "C28") (pin "2") (pinfunction "C2_2") (pintype "passive"))
      (node (ref "C29") (pin "1") (pinfunction "C1_1") (pintype "passive"))
      (node (ref "L7") (pin "1") (pinfunction "1_1") (pintype "passive"))
      (node (ref "U5") (pin "4") (pinfunction "RFIN_4") (pintype "bidirectional"))
    )
    (net (code "35") (name "Net-(C30-C2)") (class "Default")
      (node (ref "C30") (pin "2") (pinfunction "C2_2") (pintype "passive"))
      (node (ref "U6") (pin "1") (pinfunction "RFIN_1") (pintype "bidirectional"))
    )
    (net (code "36") (name "Net-(C35-C1)") (class "Default")
      (node (ref "C35") (pin "1") (pinfunction "C1_1") (pintype "passive"))
      (node (ref "L9") (pin "1") (pinfunction "1_1") (pintype "passive"))
      (node (ref "U6") (pin "3") (pinfunction "RFOUT_3") (pintype "bidirectional"))
    )
    (net (code "37") (name "Net-(C35-C2)") (class "Default")
      (node (ref "C35") (pin "2") (pinfunction "C2_2") (pintype "passive"))
      (node (ref "U7") (pin "1") (pinfunction "RFIN_1") (pintype "bidirectional"))
    )
    (net (code "38") (name "Net-(C39-C1)") (class "Default")
      (node (ref "C39") (pin "1") (pinfunction "C1_1") (pintype "passive"))
      (node (ref "L10") (pin "1") (pinfunction "1_1") (pintype "passive"))
      (node (ref "U7") (pin "3") (pinfunction "RFOUT_3") (pintype "bidirectional"))
    )
    (net (code "39") (name "Net-(C39-C2)") (class "Default")
      (node (ref "C39") (pin "2") (pinfunction "C2_2") (pintype "passive"))
      (node (ref "U8") (pin "5") (pinfunction "RFIN_5") (pintype "bidirectional"))
    )
    (net (code "40") (name "Net-(C40-C1)") (class "Default")
      (node (ref "C40") (pin "1") (pinfunction "C1_1") (pintype "passive"))
      (node (ref "TP1") (pin "TP") (pinfunction "TP_TP") (pintype "input"))
      (node (ref "U8") (pin "13") (pinfunction "VGG_13") (pintype "bidirectional"))
    )
    (net (code "41") (name "Net-(C43-C1)") (class "Default")
      (node (ref "C43") (pin "1") (pinfunction "C1_1") (pintype "passive"))
      (node (ref "C44") (pin "1") (pinfunction "C1_1") (pintype "passive"))
      (node (ref "C46") (pin "1") (pinfunction "C1_1") (pintype "passive"))
      (node (ref "U8") (pin "15") (pinfunction "AGC3_15") (pintype "bidirectional"))
    )
    (net (code "42") (name "Net-(C45-C1)") (class "Default")
      (node (ref "C45") (pin "1") (pinfunction "C1_1") (pintype "passive"))
      (node (ref "L11") (pin "1") (pinfunction "1_1") (pintype "passive"))
      (node (ref "U8") (pin "21") (pinfunction "RFOUT_21") (pintype "bidirectional"))
    )
    (net (code "43") (name "Net-(C45-C2)") (class "Default")
      (node (ref "C45") (pin "2") (pinfunction "C2_2") (pintype "passive"))
      (node (ref "RFCON2") (pin "SIG") (pinfunction "SIGNAL_SIG") (pintype "bidirectional"))
    )
    (net (code "44") (name "Net-(C47-C1)") (class "Default")
      (node (ref "C47") (pin "1") (pinfunction "C1_1") (pintype "passive"))
      (node (ref "C48") (pin "1") (pinfunction "C1_1") (pintype "passive"))
      (node (ref "U8") (pin "29") (pinfunction "AGC2_29") (pintype "bidirectional"))
    )
    (net (code "45") (name "Net-(C49-C1)") (class "Default")
      (node (ref "C49") (pin "1") (pinfunction "C1_1") (pintype "passive"))
      (node (ref "U8") (pin "30") (pinfunction "AGC1_30") (pintype "bidirectional"))
    )
    (net (code "46") (name "Net-(C55-C1)") (class "Default")
      (node (ref "C55") (pin "1") (pinfunction "C1_1") (pintype "passive"))
      (node (ref "U9") (pin "6") (pinfunction "SS_6") (pintype "bidirectional"))
    )
    (net (code "47") (name "Net-(C57-C1)") (class "Default")
      (node (ref "C57") (pin "1") (pinfunction "C1_1") (pintype "passive"))
      (node (ref "U10") (pin "15") (pinfunction "SYNC/MODE_15") (pintype "bidirectional"))
      (node (ref "U10") (pin "3") (pinfunction "INTVCC_3") (pintype "bidirectional"))
    )
    (net (code "48") (name "Net-(C58-C1)") (class "Default")
      (node (ref "C58") (pin "1") (pinfunction "C1_1") (pintype "passive"))
      (node (ref "U10") (pin "18") (pinfunction "TR/SS_18") (pintype "bidirectional"))
    )
    (net (code "49") (name "Net-(C61-C1)") (class "Default")
      (node (ref "C61") (pin "1") (pinfunction "C1_1") (pintype "passive"))
      (node (ref "L13") (pin "1") (pinfunction "1_1") (pintype "passive"))
      (node (ref "U10") (pin "10") (pinfunction "SW_10") (pintype "bidirectional"))
      (node (ref "U10") (pin "8") (pinfunction "SW_8") (pintype "bidirectional"))
      (node (ref "U10") (pin "9") (pinfunction "SW_9") (pintype "bidirectional"))
    )
    (net (code "50") (name "Net-(C61-C2)") (class "Default")
      (node (ref "C61") (pin "2") (pinfunction "C2_2") (pintype "passive"))
      (node (ref "U10") (pin "7") (pinfunction "BST_7") (pintype "bidirectional"))
    )
    (net (code "51") (name "Net-(C62-C2)") (class "Default")
      (node (ref "C62") (pin "2") (pinfunction "C2_2") (pintype "passive"))
      (node (ref "R27") (pin "1") (pinfunction "1_1") (pintype "passive"))
      (node (ref "R28") (pin "2") (pinfunction "2_2") (pintype "passive"))
      (node (ref "U10") (pin "19") (pinfunction "FB_19") (pintype "bidirectional"))
      (node (ref "U10") (pin "20") (pinfunction "FB_20") (pintype "bidirectional"))
    )
    (net (code "52") (name "Net-(C73-C2)") (class "Default")
      (node (ref "C73") (pin "2") (pinfunction "C2_2") (pintype "passive"))
      (node (ref "R35") (pin "1") (pinfunction "1_1") (pintype "passive"))
      (node (ref "R36") (pin "2") (pinfunction "2_2") (pintype "passive"))
      (node (ref "U11") (pin "3") (pinfunction "FB_3") (pintype "bidirectional"))
    )
    (net (code "53") (name "Net-(C74-C1)") (class "Default")
      (node (ref "C74") (pin "1") (pinfunction "C1_1") (pintype "passive"))
      (node (ref "U12") (pin "15") (pinfunction "SYNC/MODE_15") (pintype "bidirectional"))
      (node (ref "U12") (pin "3") (pinfunction "INTVCC_3") (pintype "bidirectional"))
    )
    (net (code "54") (name "Net-(C75-C1)") (class "Default")
      (node (ref "C75") (pin "1") (pinfunction "C1_1") (pintype "passive"))
      (node (ref "U12") (pin "18") (pinfunction "TR/SS_18") (pintype "bidirectional"))
    )
    (net (code "55") (name "Net-(C76-C1)") (class "Default")
      (node (ref "C76") (pin "1") (pinfunction "C1_1") (pintype "passive"))
      (node (ref "L14") (pin "1") (pinfunction "1_1") (pintype "passive"))
      (node (ref "U12") (pin "10") (pinfunction "SW_10") (pintype "bidirectional"))
      (node (ref "U12") (pin "8") (pinfunction "SW_8") (pintype "bidirectional"))
      (node (ref "U12") (pin "9") (pinfunction "SW_9") (pintype "bidirectional"))
    )
    (net (code "56") (name "Net-(C76-C2)") (class "Default")
      (node (ref "C76") (pin "2") (pinfunction "C2_2") (pintype "passive"))
      (node (ref "U12") (pin "7") (pinfunction "BST_7") (pintype "bidirectional"))
    )
    (net (code "57") (name "Net-(C77-C2)") (class "Default")
      (node (ref "C77") (pin "2") (pinfunction "C2_2") (pintype "passive"))
      (node (ref "R39") (pin "1") (pinfunction "1_1") (pintype "passive"))
      (node (ref "R40") (pin "2") (pinfunction "2_2") (pintype "passive"))
      (node (ref "U12") (pin "19") (pinfunction "FB_19") (pintype "bidirectional"))
      (node (ref "U12") (pin "20") (pinfunction "FB_20") (pintype "bidirectional"))
    )
    (net (code "58") (name "Net-(CON1B-S)") (class "Default")
      (node (ref "CON1") (pin "P$2") (pinfunction "S_P$2") (pintype "passive"))
      (node (ref "F1") (pin "2") (pinfunction "2_2") (pintype "passive"))
    )
    (net (code "59") (name "Net-(D1-PadA)") (class "Default")
      (node (ref "D1") (pin "A") (pinfunction "A_A") (pintype "passive"))
      (node (ref "R2") (pin "1") (pinfunction "1_1") (pintype "passive"))
    )
    (net (code "60") (name "Net-(D2-PadA)") (class "Default")
      (node (ref "D2") (pin "A") (pinfunction "A_A") (pintype "passive"))
      (node (ref "R14") (pin "1") (pinfunction "1_1") (pintype "passive"))
    )
    (net (code "61") (name "Net-(D3-PadA)") (class "Default")
      (node (ref "D3") (pin "A") (pinfunction "A_A") (pintype "passive"))
      (node (ref "R15") (pin "1") (pinfunction "1_1") (pintype "passive"))
    )
    (net (code "62") (name "Net-(D4-PadA)") (class "Default")
      (node (ref "D4") (pin "A") (pinfunction "A_A") (pintype "passive"))
      (node (ref "R30") (pin "1") (pinfunction "1_1") (pintype "passive"))
    )
    (net (code "63") (name "Net-(Q1-D)") (class "Default")
      (node (ref "Q1") (pin "3") (pinfunction "D_3") (pintype "passive"))
      (node (ref "R33") (pin "1") (pinfunction "1_1") (pintype "passive"))
    )
    (net (code "64") (name "Net-(Q1-G)") (class "Default")
      (node (ref "Q1") (pin "1") (pinfunction "G_1") (pintype "passive"))
      (node (ref "R29") (pin "1") (pinfunction "1_1") (pintype "passive"))
      (node (ref "R31") (pin "2") (pinfunction "2_2") (pintype "passive"))
    )
    (net (code "65") (name "Net-(Q2-G)") (class "Default")
      (node (ref "Q2") (pin "1") (pinfunction "G_1") (pintype "passive"))
      (node (ref "R32") (pin "1") (pinfunction "1_1") (pintype "passive"))
      (node (ref "R33") (pin "2") (pinfunction "2_2") (pintype "passive"))
    )
    (net (code "66") (name "Net-(U1-VREGSW)") (class "Default")
      (node (ref "L1") (pin "2") (pinfunction "2_2") (pintype "passive"))
      (node (ref "U1") (pin "26") (pinfunction "VREGSW_26") (pintype "bidirectional"))
    )
    (net (code "67") (name "Net-(U3-RSET)") (class "Default")
      (node (ref "R5") (pin "2") (pinfunction "2_2") (pintype "passive"))
      (node (ref "U3") (pin "22") (pinfunction "RSET_22") (pintype "bidirectional"))
    )
    (net (code "68") (name "Net-(U3-SW)") (class "Default")
      (node (ref "R6") (pin "2") (pinfunction "2_2") (pintype "passive"))
      (node (ref "U3") (pin "5") (pinfunction "SW_5") (pintype "bidirectional"))
    )
    (net (code "69") (name "Net-(U4-IFIN)") (class "Default")
      (node (ref "R12") (pin "1") (pinfunction "1_1") (pintype "passive"))
      (node (ref "R13") (pin "2") (pinfunction "2_2") (pintype "passive"))
      (node (ref "U4") (pin "3") (pinfunction "IFIN_3") (pintype "bidirectional"))
    )
    (net (code "70") (name "Net-(U4-RFOUT)") (class "Default")
      (node (ref "L5") (pin "1") (pinfunction "1_1") (pintype "passive"))
      (node (ref "U4") (pin "4") (pinfunction "RFOUT_4") (pintype "bidirectional"))
    )
    (net (code "71") (name "Net-(U9-FB)") (class "Default")
      (node (ref "R23") (pin "1") (pinfunction "1_1") (pintype "passive"))
      (node (ref "R24") (pin "2") (pinfunction "2_2") (pintype "passive"))
      (node (ref "U9") (pin "4") (pinfunction "FB_4") (pintype "bidirectional"))
    )
    (net (code "72") (name "Net-(U9-SW)") (class "Default")
      (node (ref "L12") (pin "1") (pinfunction "1_1") (pintype "passive"))
      (node (ref "U9") (pin "1") (pinfunction "SW_1") (pintype "bidirectional"))
    )
    (net (code "73") (name "Net-(U10-RT)") (class "Default")
      (node (ref "R20") (pin "2") (pinfunction "2_2") (pintype "passive"))
      (node (ref "U10") (pin "17") (pinfunction "RT_17") (pintype "bidirectional"))
    )
    (net (code "74") (name "Net-(U12-RT)") (class "Default")
      (node (ref "R37") (pin "2") (pinfunction "2_2") (pintype "passive"))
      (node (ref "U12") (pin "17") (pinfunction "RT_17") (pintype "bidirectional"))
    )
    (net (code "75") (name "PLL_EN") (class "Default")
      (node (ref "R3") (pin "2") (pinfunction "2_2") (pintype "passive"))
      (node (ref "U1") (pin "10") (pinfunction "PD9_10") (pintype "bidirectional"))
      (node (ref "U3") (pin "4") (pinfunction "CE_4") (pintype "bidirectional"))
    )
    (net (code "76") (name "PLL_LE") (class "Default")
      (node (ref "U1") (pin "11") (pinfunction "PD10_11") (pintype "bidirectional"))
      (node (ref "U3") (pin "3") (pinfunction "LE_3") (pintype "bidirectional"))
    )
    (net (code "77") (name "PLL_LOCK") (class "Default")
      (node (ref "U1") (pin "16") (pinfunction "PD15_16") (pintype "bidirectional"))
      (node (ref "U3") (pin "25") (pinfunction "LD_25") (pintype "bidirectional"))
    )
    (net (code "78") (name "PLL_MUXOUT") (class "Default")
      (node (ref "U1") (pin "14") (pinfunction "PD13_14") (pintype "bidirectional"))
      (node (ref "U3") (pin "30") (pinfunction "MUXOUT_30") (pintype "bidirectional"))
    )
    (net (code "79") (name "PLL_SCLK") (class "Default")
      (node (ref "U1") (pin "13") (pinfunction "PD12_13") (pintype "bidirectional"))
      (node (ref "U3") (pin "1") (pinfunction "CLK_1") (pintype "bidirectional"))
    )
    (net (code "80") (name "PLL_SDATA") (class "Default")
      (node (ref "U1") (pin "12") (pinfunction "PD11_12") (pintype "bidirectional"))
      (node (ref "U3") (pin "2") (pinfunction "DATA_2") (pintype "bidirectional"))
    )
    (net (code "81") (name "RF_ACC_FILT") (class "Default")
      (node (ref "C30") (pin "1") (pinfunction "C1_1") (pintype "passive"))
      (node (ref "L8") (pin "1") (pinfunction "1_1") (pintype "passive"))
      (node (ref "U5") (pin "2") (pinfunction "RFOUT_2") (pintype "bidirectional"))
    )
    (net (code "82") (name "SWCLK") (class "Default")
      (node (ref "TC1") (pin "4") (pinfunction "S_4") (pintype "passive"))
      (node (ref "U1") (pin "1") (pinfunction "PF0_1") (pintype "bidirectional"))
    )
    (net (code "83") (name "SWDIO") (class "Default")
      (node (ref "TC1") (pin "2") (pinfunction "S_2") (pintype "passive"))
      (node (ref "U1") (pin "2") (pinfunction "PF1_2") (pintype "bidirectional"))
    )
    (net (code "84") (name "SWO") (class "Default")
      (node (ref "TC1") (pin "6") (pinfunction "S_6") (pintype "passive"))
      (node (ref "U1") (pin "3") (pinfunction "PF2_3") (pintype "bidirectional"))
    )
    (net (code "85") (name "VIN") (class "Default")
      (node (ref "C51") (pin "1") (pinfunction "C1_1") (pintype "passive"))
      (node (ref "C54") (pin "1") (pinfunction "C1_1") (pintype "passive"))
      (node (ref "C56") (pin "1") (pinfunction "C1_1") (pintype "passive"))
      (node (ref "C68") (pin "1") (pinfunction "C1_1") (pintype "passive"))
      (node (ref "C70") (pin "1") (pinfunction "C1_1") (pintype "passive"))
      (node (ref "C72") (pin "1") (pinfunction "C1_1") (pintype "passive"))
      (node (ref "C85") (pin "1") (pinfunction "C1_1") (pintype "passive"))
      (node (ref "D5") (pin "C") (pinfunction "C_C") (pintype "passive"))
      (node (ref "F1") (pin "1") (pinfunction "1_1") (pintype "passive"))
      (node (ref "R16") (pin "2") (pinfunction "2_2") (pintype "passive"))
      (node (ref "U10") (pin "11") (pinfunction "VIN_11") (pintype "bidirectional"))
      (node (ref "U10") (pin "14") (pinfunction "EN/UV_14") (pintype "bidirectional"))
      (node (ref "U10") (pin "6") (pinfunction "VIN_6") (pintype "bidirectional"))
      (node (ref "U12") (pin "11") (pinfunction "VIN_11") (pintype "bidirectional"))
      (node (ref "U12") (pin "14") (pinfunction "EN/UV_14") (pintype "bidirectional"))
      (node (ref "U12") (pin "6") (pinfunction "VIN_6") (pintype "bidirectional"))
    )
    (net (code "86") (name "VIN_VSENSE") (class "Default")
      (node (ref "C53") (pin "1") (pinfunction "C1_1") (pintype "passive"))
      (node (ref "R16") (pin "1") (pinfunction "1_1") (pintype "passive"))
      (node (ref "R17") (pin "2") (pinfunction "2_2") (pintype "passive"))
      (node (ref "U1") (pin "21") (pinfunction "PB13_21") (pintype "bidirectional"))
    )
    (net (code "87") (name "unconnected-(TC1F-S-Pad5)") (class "Default")
      (node (ref "TC1") (pin "5") (pinfunction "S_5") (pintype "passive"))
    )
    (net (code "88") (name "unconnected-(U1-HFXTAL_N-Pad6)") (class "Default")
      (node (ref "U1") (pin "6") (pinfunction "HFXTAL_N_6") (pintype "bidirectional"))
    )
    (net (code "89") (name "unconnected-(U1-HFXTAL_P-Pad7)") (class "Default")
      (node (ref "U1") (pin "7") (pinfunction "HFXTAL_P_7") (pintype "bidirectional"))
    )
    (net (code "90") (name "unconnected-(U3-RFOUTB+-Pad14)") (class "Default")
      (node (ref "U3") (pin "14") (pinfunction "RFOUTB+_14") (pintype "bidirectional"))
    )
    (net (code "91") (name "unconnected-(U3-RFOUTB--Pad15)") (class "Default")
      (node (ref "U3") (pin "15") (pinfunction "RFOUTB-_15") (pintype "bidirectional"))
    )
    (net (code "92") (name "unconnected-(U9-PG-Pad5)") (class "Default")
      (node (ref "U9") (pin "5") (pinfunction "PG_5") (pintype "bidirectional"))
    )
    (net (code "93") (name "unconnected-(U10-CLKOUT-Pad16)") (class "Default")
      (node (ref "U10") (pin "16") (pinfunction "CLKOUT_16") (pintype "bidirectional"))
    )
    (net (code "94") (name "unconnected-(U12-CLKOUT-Pad16)") (class "Default")
      (node (ref "U12") (pin "16") (pinfunction "CLKOUT_16") (pintype "bidirectional"))
    )
    (net (code "95") (name "~{5V0_PA_BIAS_EN}") (class "Default")
      (node (ref "R34") (pin "1") (pinfunction "1_1") (pintype "passive"))
      (node (ref "U1") (pin "17") (pinfunction "PA0_17") (pintype "bidirectional"))
      (node (ref "U11") (pin "6") (pinfunction "SD_6") (pintype "bidirectional"))
    )
    (net (code "96") (name "~{MIXER_SHDN}") (class "Default")
      (node (ref "R9") (pin "2") (pinfunction "2_2") (pintype "passive"))
      (node (ref "U1") (pin "4") (pinfunction "PF3_4") (pintype "bidirectional"))
    )
    (net (code "97") (name "~{PLL_MUTE}") (class "Default")
      (node (ref "R4") (pin "2") (pinfunction "2_2") (pintype "passive"))
      (node (ref "U1") (pin "15") (pinfunction "PD14_15") (pintype "bidirectional"))
      (node (ref "U3") (pin "26") (pinfunction "~{PDRF}_26") (pintype "bidirectional"))
    )
    (net (code "98") (name "~{RESET}") (class "Default")
      (node (ref "R1") (pin "1") (pinfunction "1_1") (pintype "passive"))
      (node (ref "TC1") (pin "10") (pinfunction "S_10") (pintype "passive"))
      (node (ref "U1") (pin "8") (pinfunction "~{RESET}_8") (pintype "bidirectional"))
    )
  )
)
